# PCB-Relay-Board-V1.net
KiCad netlist of a schematic drawn in Altium Designer
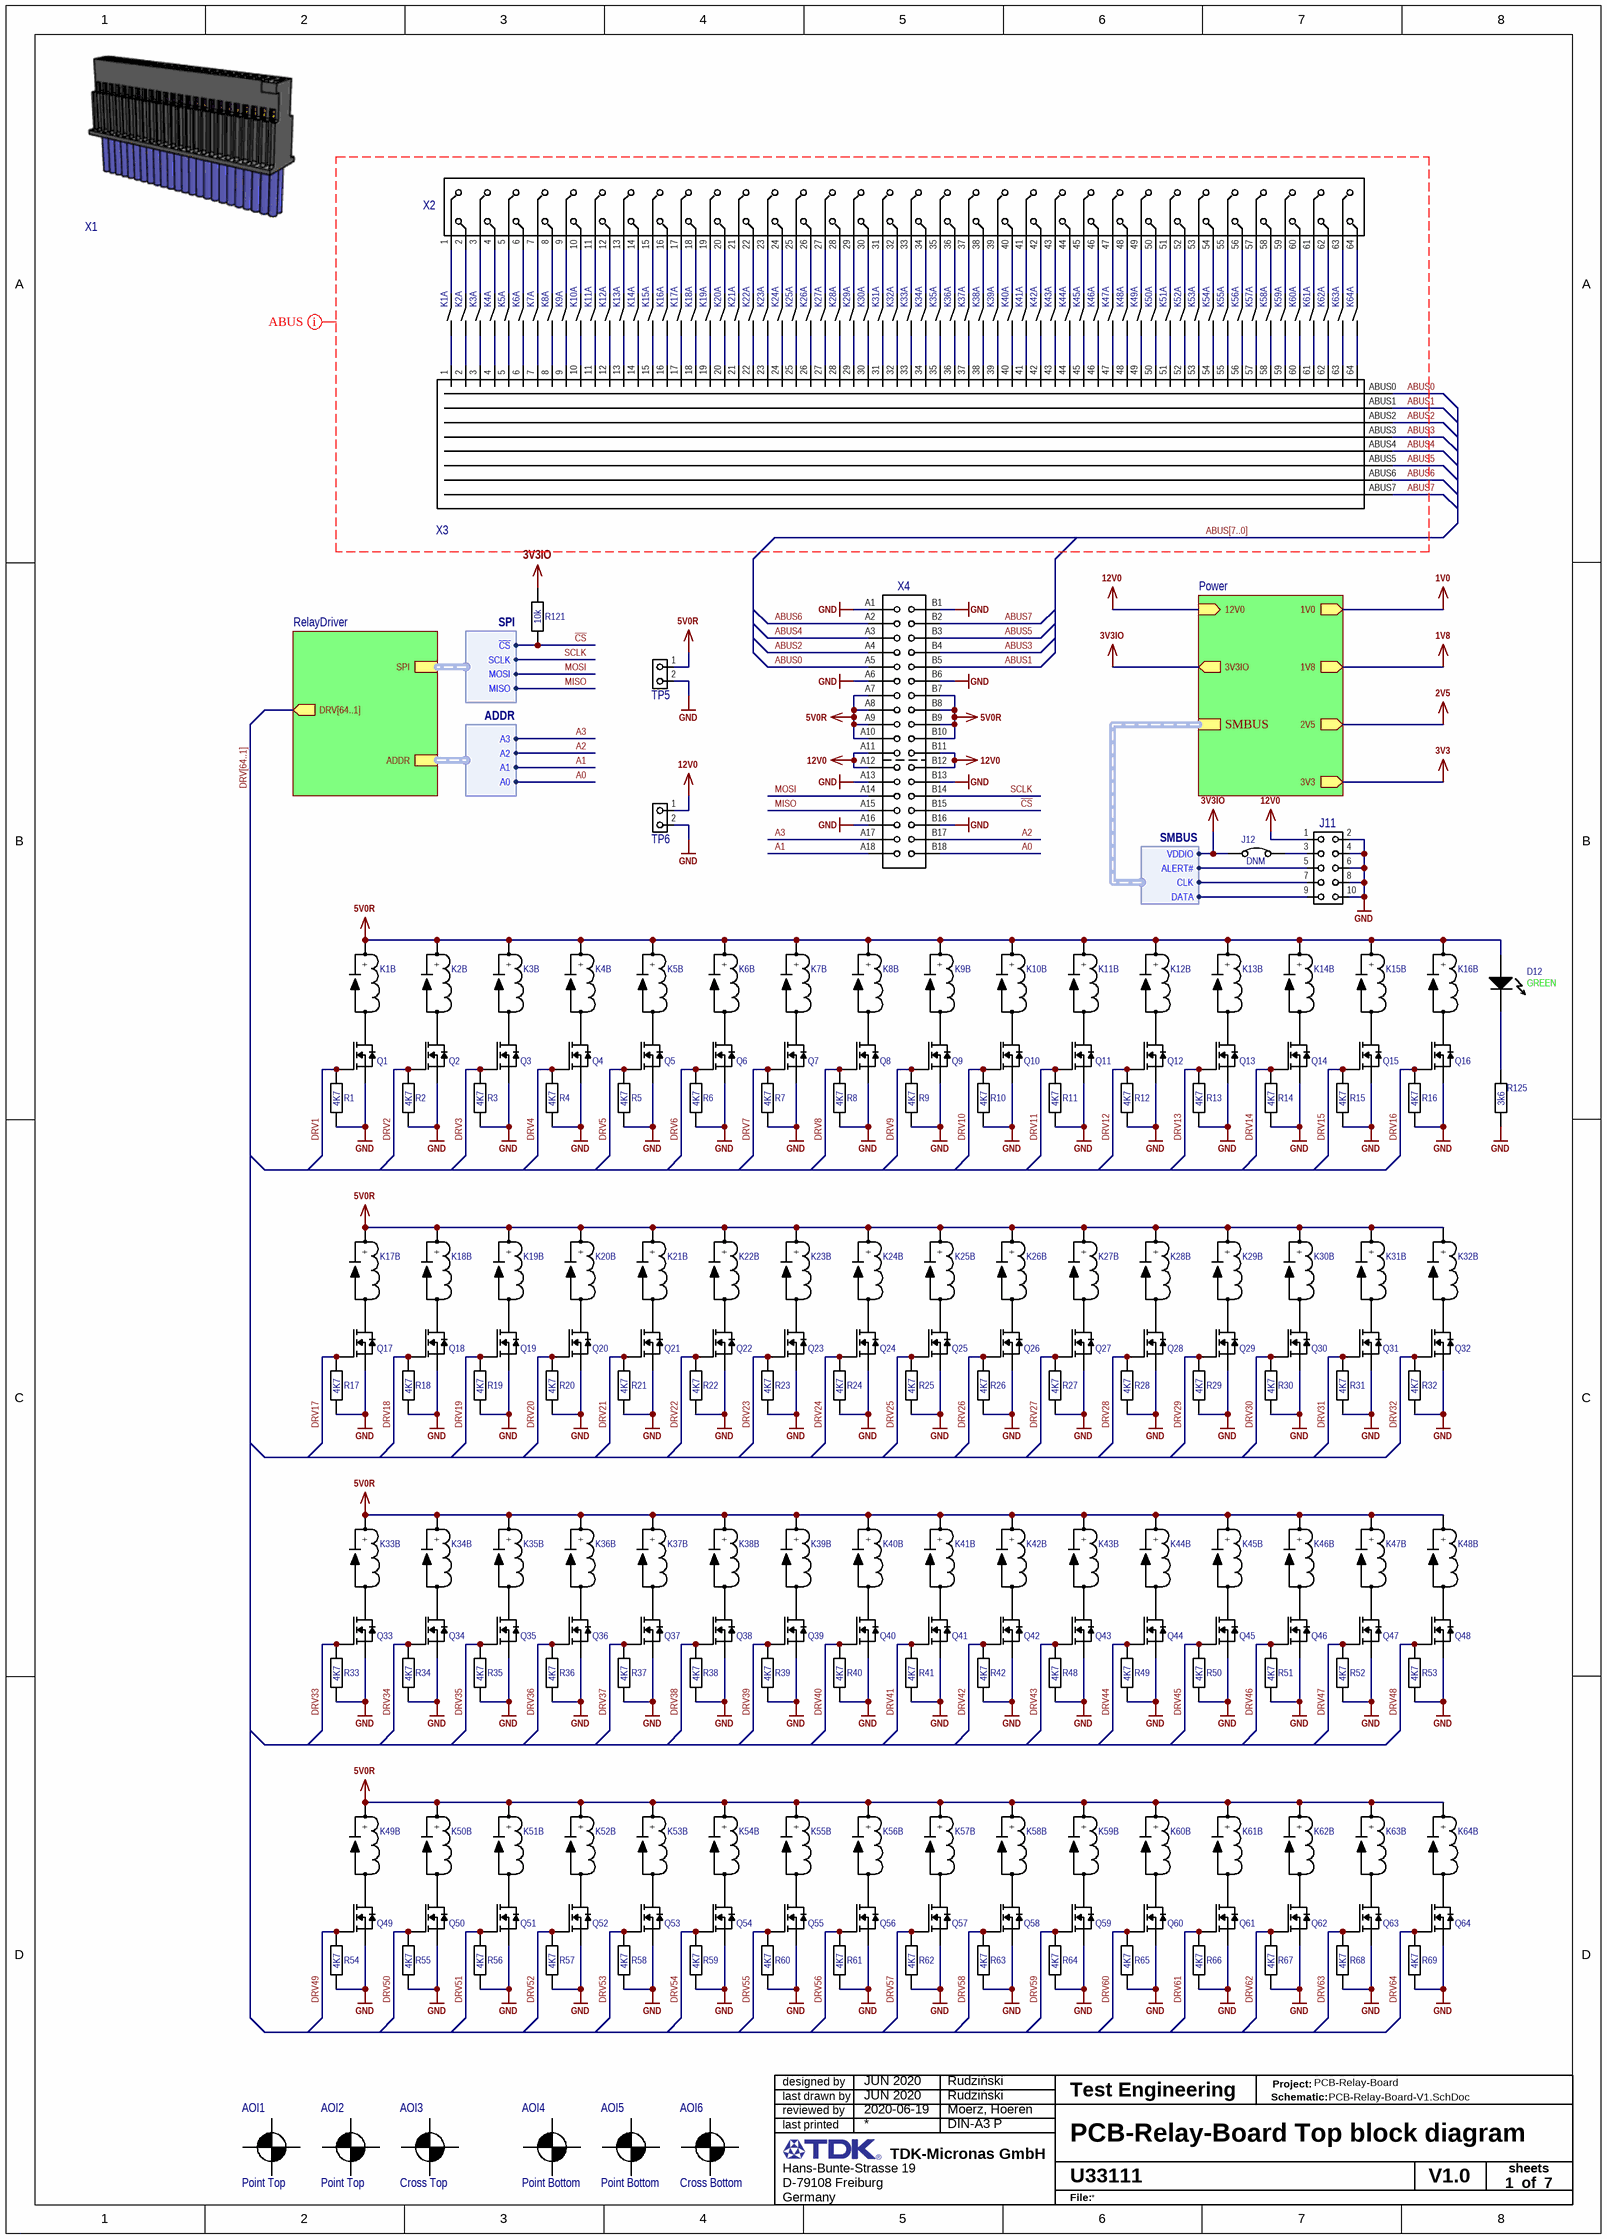
[diagram p0: PCB-Relay-Board-V1.SchDoc]

(export (version "E")
  (design (tool "Eeschema 10.0.6"))
  (components
    (comp (ref "AOI1")
      (value "AOI")
      (footprint "Fiducial Point")
      (description "Assembly AOI")
      (fields (field (name "SHAPE") "Point Top") (field (name "13. CREATED DATE/NAME") "AUG2018/Hören"))
      (libsource (lib "chickenfood") (part "Fiducial"))
    )
    (comp (ref "AOI2")
      (value "AOI")
      (footprint "Fiducial Point")
      (description "Assembly AOI")
      (fields (field (name "SHAPE") "Point Top") (field (name "13. CREATED DATE/NAME") "AUG2018/Hören"))
      (libsource (lib "chickenfood") (part "Fiducial"))
    )
    (comp (ref "AOI3")
      (value "AOI")
      (footprint "Fiducial Cross")
      (description "Assembly AOI")
      (fields (field (name "SHAPE") "Cross Top") (field (name "13. CREATED DATE/NAME") "AUG2018/Hören"))
      (libsource (lib "chickenfood") (part "Fiducial"))
    )
    (comp (ref "AOI4")
      (value "AOI")
      (footprint "Fiducial Point")
      (description "Assembly AOI")
      (fields (field (name "SHAPE") "Point Bottom") (field (name "13. CREATED DATE/NAME") "AUG2018/Hören"))
      (libsource (lib "chickenfood") (part "Fiducial"))
    )
    (comp (ref "AOI5")
      (value "AOI")
      (footprint "Fiducial Point")
      (description "Assembly AOI")
      (fields (field (name "SHAPE") "Point Bottom") (field (name "13. CREATED DATE/NAME") "AUG2018/Hören"))
      (libsource (lib "chickenfood") (part "Fiducial"))
    )
    (comp (ref "AOI6")
      (value "AOI")
      (footprint "Fiducial Cross")
      (description "Assembly AOI")
      (fields (field (name "SHAPE") "Cross Bottom") (field (name "13. CREATED DATE/NAME") "AUG2018/Hören"))
      (libsource (lib "chickenfood") (part "Fiducial"))
    )
    (comp (ref "D12")
      (value "D")
      (footprint "L0603G")
      (description "LED GREEN DIFFUSED 0603 SMD")
      (fields
        (field (name "02. DISTRIBUTOR PART NUMBER") "475-2709-6-ND")
        (field (name "07. MANUFACTURER  PART NUMBER") "LG L29K-G2J1-24-Z")
        (field (name "COLOR") "GREEN")
        (field (name "13. CREATED DATE/NAME") "AUG2018/Hören")
      )
      (libsource (lib "chickenfood") (part "LED"))
    )
    (comp (ref "J11")
      (value "J")
      (footprint "Header 100mil 5x2")
      (description ".100\" High-Temp Variable Post Height Terminal Strip")
      (fields
        (field (name "02. DISTRIBUTOR PART NUMBER") "HMTSW-105-07-G-D-240")
        (field (name "13. CREATED DATE/NAME") "AUG2018/Hören")
      )
      (libsource (lib "PCB-Tester-Board-V1") (part "Header 5x2Pins 100mil"))
    )
    (comp (ref "J12")
      (value "DNM")
      (footprint "JumperSMD")
      (description "RES SMD 0 OHM JUMPER 1/10W 0603")
      (fields
        (field (name "02. DISTRIBUTOR PART NUMBER") "311-0.0GRDKR-ND")
        (field (name "07. MANUFACTURER  PART NUMBER") "RC0603JR-070RL")
      )
      (libsource (lib "chickenfood") (part "Jumper SMD"))
    )
    (comp (ref "K1")
      (value "K")
      (footprint "118-1A")
      (description "5V Signal Relais, Normal Open")
      (fields
        (field (name "02. DISTRIBUTOR PART NUMBER") "118-1-A-5/2D")
        (field (name "13. CREATED DATE/NAME") "20.12.17 S. Kaiser")
      )
      (libsource (lib "") (part "118-1-A-5/2D_1"))
    )
    (comp (ref "K2")
      (value "K")
      (footprint "118-1A")
      (description "5V Signal Relais, Normal Open")
      (fields
        (field (name "02. DISTRIBUTOR PART NUMBER") "118-1-A-5/2D")
        (field (name "13. CREATED DATE/NAME") "20.12.17 S. Kaiser")
      )
      (libsource (lib "") (part "118-1-A-5/2D_1"))
    )
    (comp (ref "K3")
      (value "K")
      (footprint "118-1A")
      (description "5V Signal Relais, Normal Open")
      (fields
        (field (name "02. DISTRIBUTOR PART NUMBER") "118-1-A-5/2D")
        (field (name "13. CREATED DATE/NAME") "20.12.17 S. Kaiser")
      )
      (libsource (lib "") (part "118-1-A-5/2D_1"))
    )
    (comp (ref "K4")
      (value "K")
      (footprint "118-1A")
      (description "5V Signal Relais, Normal Open")
      (fields
        (field (name "02. DISTRIBUTOR PART NUMBER") "118-1-A-5/2D")
        (field (name "13. CREATED DATE/NAME") "20.12.17 S. Kaiser")
      )
      (libsource (lib "") (part "118-1-A-5/2D_1"))
    )
    (comp (ref "K5")
      (value "K")
      (footprint "118-1A")
      (description "5V Signal Relais, Normal Open")
      (fields
        (field (name "02. DISTRIBUTOR PART NUMBER") "118-1-A-5/2D")
        (field (name "13. CREATED DATE/NAME") "20.12.17 S. Kaiser")
      )
      (libsource (lib "chickenfood") (part "118-1-A-5/2D"))
    )
    (comp (ref "K6")
      (value "K")
      (footprint "118-1A")
      (description "5V Signal Relais, Normal Open")
      (fields
        (field (name "02. DISTRIBUTOR PART NUMBER") "118-1-A-5/2D")
        (field (name "13. CREATED DATE/NAME") "20.12.17 S. Kaiser")
      )
      (libsource (lib "chickenfood") (part "118-1-A-5/2D"))
    )
    (comp (ref "K7")
      (value "K")
      (footprint "118-1A")
      (description "5V Signal Relais, Normal Open")
      (fields
        (field (name "02. DISTRIBUTOR PART NUMBER") "118-1-A-5/2D")
        (field (name "13. CREATED DATE/NAME") "20.12.17 S. Kaiser")
      )
      (libsource (lib "chickenfood") (part "118-1-A-5/2D"))
    )
    (comp (ref "K8")
      (value "K")
      (footprint "118-1A")
      (description "5V Signal Relais, Normal Open")
      (fields
        (field (name "02. DISTRIBUTOR PART NUMBER") "118-1-A-5/2D")
        (field (name "13. CREATED DATE/NAME") "20.12.17 S. Kaiser")
      )
      (libsource (lib "") (part "118-1-A-5/2D_1"))
    )
    (comp (ref "K9")
      (value "K")
      (footprint "118-1A")
      (description "5V Signal Relais, Normal Open")
      (fields
        (field (name "02. DISTRIBUTOR PART NUMBER") "118-1-A-5/2D")
        (field (name "13. CREATED DATE/NAME") "20.12.17 S. Kaiser")
      )
      (libsource (lib "chickenfood") (part "118-1-A-5/2D"))
    )
    (comp (ref "K10")
      (value "K")
      (footprint "118-1A")
      (description "5V Signal Relais, Normal Open")
      (fields
        (field (name "02. DISTRIBUTOR PART NUMBER") "118-1-A-5/2D")
        (field (name "13. CREATED DATE/NAME") "20.12.17 S. Kaiser")
      )
      (libsource (lib "chickenfood") (part "118-1-A-5/2D"))
    )
    (comp (ref "K11")
      (value "K")
      (footprint "118-1A")
      (description "5V Signal Relais, Normal Open")
      (fields
        (field (name "02. DISTRIBUTOR PART NUMBER") "118-1-A-5/2D")
        (field (name "13. CREATED DATE/NAME") "20.12.17 S. Kaiser")
      )
      (libsource (lib "chickenfood") (part "118-1-A-5/2D"))
    )
    (comp (ref "K12")
      (value "K")
      (footprint "118-1A")
      (description "5V Signal Relais, Normal Open")
      (fields
        (field (name "02. DISTRIBUTOR PART NUMBER") "118-1-A-5/2D")
        (field (name "13. CREATED DATE/NAME") "20.12.17 S. Kaiser")
      )
      (libsource (lib "chickenfood") (part "118-1-A-5/2D"))
    )
    (comp (ref "K13")
      (value "K")
      (footprint "118-1A")
      (description "5V Signal Relais, Normal Open")
      (fields
        (field (name "02. DISTRIBUTOR PART NUMBER") "118-1-A-5/2D")
        (field (name "13. CREATED DATE/NAME") "20.12.17 S. Kaiser")
      )
      (libsource (lib "") (part "118-1-A-5/2D_1"))
    )
    (comp (ref "K14")
      (value "K")
      (footprint "118-1A")
      (description "5V Signal Relais, Normal Open")
      (fields
        (field (name "02. DISTRIBUTOR PART NUMBER") "118-1-A-5/2D")
        (field (name "13. CREATED DATE/NAME") "20.12.17 S. Kaiser")
      )
      (libsource (lib "chickenfood") (part "118-1-A-5/2D"))
    )
    (comp (ref "K15")
      (value "K")
      (footprint "118-1A")
      (description "5V Signal Relais, Normal Open")
      (fields
        (field (name "02. DISTRIBUTOR PART NUMBER") "118-1-A-5/2D")
        (field (name "13. CREATED DATE/NAME") "20.12.17 S. Kaiser")
      )
      (libsource (lib "") (part "118-1-A-5/2D_1"))
    )
    (comp (ref "K16")
      (value "K")
      (footprint "118-1A")
      (description "5V Signal Relais, Normal Open")
      (fields
        (field (name "02. DISTRIBUTOR PART NUMBER") "118-1-A-5/2D")
        (field (name "13. CREATED DATE/NAME") "20.12.17 S. Kaiser")
      )
      (libsource (lib "chickenfood") (part "118-1-A-5/2D"))
    )
    (comp (ref "K17")
      (value "K")
      (footprint "118-1A")
      (description "5V Signal Relais, Normal Open")
      (fields
        (field (name "02. DISTRIBUTOR PART NUMBER") "118-1-A-5/2D")
        (field (name "13. CREATED DATE/NAME") "20.12.17 S. Kaiser")
      )
      (libsource (lib "chickenfood") (part "118-1-A-5/2D"))
    )
    (comp (ref "K18")
      (value "K")
      (footprint "118-1A")
      (description "5V Signal Relais, Normal Open")
      (fields
        (field (name "02. DISTRIBUTOR PART NUMBER") "118-1-A-5/2D")
        (field (name "13. CREATED DATE/NAME") "20.12.17 S. Kaiser")
      )
      (libsource (lib "") (part "118-1-A-5/2D_1"))
    )
    (comp (ref "K19")
      (value "K")
      (footprint "118-1A")
      (description "5V Signal Relais, Normal Open")
      (fields
        (field (name "02. DISTRIBUTOR PART NUMBER") "118-1-A-5/2D")
        (field (name "13. CREATED DATE/NAME") "20.12.17 S. Kaiser")
      )
      (libsource (lib "chickenfood") (part "118-1-A-5/2D"))
    )
    (comp (ref "K20")
      (value "K")
      (footprint "118-1A")
      (description "5V Signal Relais, Normal Open")
      (fields
        (field (name "02. DISTRIBUTOR PART NUMBER") "118-1-A-5/2D")
        (field (name "13. CREATED DATE/NAME") "20.12.17 S. Kaiser")
      )
      (libsource (lib "") (part "118-1-A-5/2D_1"))
    )
    (comp (ref "K21")
      (value "K")
      (footprint "118-1A")
      (description "5V Signal Relais, Normal Open")
      (fields
        (field (name "02. DISTRIBUTOR PART NUMBER") "118-1-A-5/2D")
        (field (name "13. CREATED DATE/NAME") "20.12.17 S. Kaiser")
      )
      (libsource (lib "chickenfood") (part "118-1-A-5/2D"))
    )
    (comp (ref "K22")
      (value "K")
      (footprint "118-1A")
      (description "5V Signal Relais, Normal Open")
      (fields
        (field (name "02. DISTRIBUTOR PART NUMBER") "118-1-A-5/2D")
        (field (name "13. CREATED DATE/NAME") "20.12.17 S. Kaiser")
      )
      (libsource (lib "") (part "118-1-A-5/2D_1"))
    )
    (comp (ref "K23")
      (value "K")
      (footprint "118-1A")
      (description "5V Signal Relais, Normal Open")
      (fields
        (field (name "02. DISTRIBUTOR PART NUMBER") "118-1-A-5/2D")
        (field (name "13. CREATED DATE/NAME") "20.12.17 S. Kaiser")
      )
      (libsource (lib "") (part "118-1-A-5/2D_1"))
    )
    (comp (ref "K24")
      (value "K")
      (footprint "118-1A")
      (description "5V Signal Relais, Normal Open")
      (fields
        (field (name "02. DISTRIBUTOR PART NUMBER") "118-1-A-5/2D")
        (field (name "13. CREATED DATE/NAME") "20.12.17 S. Kaiser")
      )
      (libsource (lib "chickenfood") (part "118-1-A-5/2D"))
    )
    (comp (ref "K25")
      (value "K")
      (footprint "118-1A")
      (description "5V Signal Relais, Normal Open")
      (fields
        (field (name "02. DISTRIBUTOR PART NUMBER") "118-1-A-5/2D")
        (field (name "13. CREATED DATE/NAME") "20.12.17 S. Kaiser")
      )
      (libsource (lib "") (part "118-1-A-5/2D_1"))
    )
    (comp (ref "K26")
      (value "K")
      (footprint "118-1A")
      (description "5V Signal Relais, Normal Open")
      (fields
        (field (name "02. DISTRIBUTOR PART NUMBER") "118-1-A-5/2D")
        (field (name "13. CREATED DATE/NAME") "20.12.17 S. Kaiser")
      )
      (libsource (lib "chickenfood") (part "118-1-A-5/2D"))
    )
    (comp (ref "K27")
      (value "K")
      (footprint "118-1A")
      (description "5V Signal Relais, Normal Open")
      (fields
        (field (name "02. DISTRIBUTOR PART NUMBER") "118-1-A-5/2D")
        (field (name "13. CREATED DATE/NAME") "20.12.17 S. Kaiser")
      )
      (libsource (lib "") (part "118-1-A-5/2D_1"))
    )
    (comp (ref "K28")
      (value "K")
      (footprint "118-1A")
      (description "5V Signal Relais, Normal Open")
      (fields
        (field (name "02. DISTRIBUTOR PART NUMBER") "118-1-A-5/2D")
        (field (name "13. CREATED DATE/NAME") "20.12.17 S. Kaiser")
      )
      (libsource (lib "chickenfood") (part "118-1-A-5/2D"))
    )
    (comp (ref "K29")
      (value "K")
      (footprint "118-1A")
      (description "5V Signal Relais, Normal Open")
      (fields
        (field (name "02. DISTRIBUTOR PART NUMBER") "118-1-A-5/2D")
        (field (name "13. CREATED DATE/NAME") "20.12.17 S. Kaiser")
      )
      (libsource (lib "chickenfood") (part "118-1-A-5/2D"))
    )
    (comp (ref "K30")
      (value "K")
      (footprint "118-1A")
      (description "5V Signal Relais, Normal Open")
      (fields
        (field (name "02. DISTRIBUTOR PART NUMBER") "118-1-A-5/2D")
        (field (name "13. CREATED DATE/NAME") "20.12.17 S. Kaiser")
      )
      (libsource (lib "") (part "118-1-A-5/2D_1"))
    )
    (comp (ref "K31")
      (value "K")
      (footprint "118-1A")
      (description "5V Signal Relais, Normal Open")
      (fields
        (field (name "02. DISTRIBUTOR PART NUMBER") "118-1-A-5/2D")
        (field (name "13. CREATED DATE/NAME") "20.12.17 S. Kaiser")
      )
      (libsource (lib "") (part "118-1-A-5/2D_1"))
    )
    (comp (ref "K32")
      (value "K")
      (footprint "118-1A")
      (description "5V Signal Relais, Normal Open")
      (fields
        (field (name "02. DISTRIBUTOR PART NUMBER") "118-1-A-5/2D")
        (field (name "13. CREATED DATE/NAME") "20.12.17 S. Kaiser")
      )
      (libsource (lib "") (part "118-1-A-5/2D_1"))
    )
    (comp (ref "K33")
      (value "K")
      (footprint "118-1A")
      (description "5V Signal Relais, Normal Open")
      (fields
        (field (name "02. DISTRIBUTOR PART NUMBER") "118-1-A-5/2D")
        (field (name "13. CREATED DATE/NAME") "20.12.17 S. Kaiser")
      )
      (libsource (lib "chickenfood") (part "118-1-A-5/2D"))
    )
    (comp (ref "K34")
      (value "K")
      (footprint "118-1A")
      (description "5V Signal Relais, Normal Open")
      (fields
        (field (name "02. DISTRIBUTOR PART NUMBER") "118-1-A-5/2D")
        (field (name "13. CREATED DATE/NAME") "20.12.17 S. Kaiser")
      )
      (libsource (lib "chickenfood") (part "118-1-A-5/2D"))
    )
    (comp (ref "K35")
      (value "K")
      (footprint "118-1A")
      (description "5V Signal Relais, Normal Open")
      (fields
        (field (name "02. DISTRIBUTOR PART NUMBER") "118-1-A-5/2D")
        (field (name "13. CREATED DATE/NAME") "20.12.17 S. Kaiser")
      )
      (libsource (lib "") (part "118-1-A-5/2D_1"))
    )
    (comp (ref "K36")
      (value "K")
      (footprint "118-1A")
      (description "5V Signal Relais, Normal Open")
      (fields
        (field (name "02. DISTRIBUTOR PART NUMBER") "118-1-A-5/2D")
        (field (name "13. CREATED DATE/NAME") "20.12.17 S. Kaiser")
      )
      (libsource (lib "chickenfood") (part "118-1-A-5/2D"))
    )
    (comp (ref "K37")
      (value "K")
      (footprint "118-1A")
      (description "5V Signal Relais, Normal Open")
      (fields
        (field (name "02. DISTRIBUTOR PART NUMBER") "118-1-A-5/2D")
        (field (name "13. CREATED DATE/NAME") "20.12.17 S. Kaiser")
      )
      (libsource (lib "chickenfood") (part "118-1-A-5/2D"))
    )
    (comp (ref "K38")
      (value "K")
      (footprint "118-1A")
      (description "5V Signal Relais, Normal Open")
      (fields
        (field (name "02. DISTRIBUTOR PART NUMBER") "118-1-A-5/2D")
        (field (name "13. CREATED DATE/NAME") "20.12.17 S. Kaiser")
      )
      (libsource (lib "") (part "118-1-A-5/2D_1"))
    )
    (comp (ref "K39")
      (value "K")
      (footprint "118-1A")
      (description "5V Signal Relais, Normal Open")
      (fields
        (field (name "02. DISTRIBUTOR PART NUMBER") "118-1-A-5/2D")
        (field (name "13. CREATED DATE/NAME") "20.12.17 S. Kaiser")
      )
      (libsource (lib "") (part "118-1-A-5/2D_1"))
    )
    (comp (ref "K40")
      (value "K")
      (footprint "118-1A")
      (description "5V Signal Relais, Normal Open")
      (fields
        (field (name "02. DISTRIBUTOR PART NUMBER") "118-1-A-5/2D")
        (field (name "13. CREATED DATE/NAME") "20.12.17 S. Kaiser")
      )
      (libsource (lib "chickenfood") (part "118-1-A-5/2D"))
    )
    (comp (ref "K41")
      (value "K")
      (footprint "118-1A")
      (description "5V Signal Relais, Normal Open")
      (fields
        (field (name "02. DISTRIBUTOR PART NUMBER") "118-1-A-5/2D")
        (field (name "13. CREATED DATE/NAME") "20.12.17 S. Kaiser")
      )
      (libsource (lib "chickenfood") (part "118-1-A-5/2D"))
    )
    (comp (ref "K42")
      (value "K")
      (footprint "118-1A")
      (description "5V Signal Relais, Normal Open")
      (fields
        (field (name "02. DISTRIBUTOR PART NUMBER") "118-1-A-5/2D")
        (field (name "13. CREATED DATE/NAME") "20.12.17 S. Kaiser")
      )
      (libsource (lib "") (part "118-1-A-5/2D_1"))
    )
    (comp (ref "K43")
      (value "K")
      (footprint "118-1A")
      (description "5V Signal Relais, Normal Open")
      (fields
        (field (name "02. DISTRIBUTOR PART NUMBER") "118-1-A-5/2D")
        (field (name "13. CREATED DATE/NAME") "20.12.17 S. Kaiser")
      )
      (libsource (lib "chickenfood") (part "118-1-A-5/2D"))
    )
    (comp (ref "K44")
      (value "K")
      (footprint "118-1A")
      (description "5V Signal Relais, Normal Open")
      (fields
        (field (name "02. DISTRIBUTOR PART NUMBER") "118-1-A-5/2D")
        (field (name "13. CREATED DATE/NAME") "20.12.17 S. Kaiser")
      )
      (libsource (lib "") (part "118-1-A-5/2D_1"))
    )
    (comp (ref "K45")
      (value "K")
      (footprint "118-1A")
      (description "5V Signal Relais, Normal Open")
      (fields
        (field (name "02. DISTRIBUTOR PART NUMBER") "118-1-A-5/2D")
        (field (name "13. CREATED DATE/NAME") "20.12.17 S. Kaiser")
      )
      (libsource (lib "chickenfood") (part "118-1-A-5/2D"))
    )
    (comp (ref "K46")
      (value "K")
      (footprint "118-1A")
      (description "5V Signal Relais, Normal Open")
      (fields
        (field (name "02. DISTRIBUTOR PART NUMBER") "118-1-A-5/2D")
        (field (name "13. CREATED DATE/NAME") "20.12.17 S. Kaiser")
      )
      (libsource (lib "chickenfood") (part "118-1-A-5/2D"))
    )
    (comp (ref "K47")
      (value "K")
      (footprint "118-1A")
      (description "5V Signal Relais, Normal Open")
      (fields
        (field (name "02. DISTRIBUTOR PART NUMBER") "118-1-A-5/2D")
        (field (name "13. CREATED DATE/NAME") "20.12.17 S. Kaiser")
      )
      (libsource (lib "chickenfood") (part "118-1-A-5/2D"))
    )
    (comp (ref "K48")
      (value "K")
      (footprint "118-1A")
      (description "5V Signal Relais, Normal Open")
      (fields
        (field (name "02. DISTRIBUTOR PART NUMBER") "118-1-A-5/2D")
        (field (name "13. CREATED DATE/NAME") "20.12.17 S. Kaiser")
      )
      (libsource (lib "chickenfood") (part "118-1-A-5/2D"))
    )
    (comp (ref "K49")
      (value "K")
      (footprint "118-1A")
      (description "5V Signal Relais, Normal Open")
      (fields
        (field (name "02. DISTRIBUTOR PART NUMBER") "118-1-A-5/2D")
        (field (name "13. CREATED DATE/NAME") "20.12.17 S. Kaiser")
      )
      (libsource (lib "chickenfood") (part "118-1-A-5/2D"))
    )
    (comp (ref "K50")
      (value "K")
      (footprint "118-1A")
      (description "5V Signal Relais, Normal Open")
      (fields
        (field (name "02. DISTRIBUTOR PART NUMBER") "118-1-A-5/2D")
        (field (name "13. CREATED DATE/NAME") "20.12.17 S. Kaiser")
      )
      (libsource (lib "chickenfood") (part "118-1-A-5/2D"))
    )
    (comp (ref "K51")
      (value "K")
      (footprint "118-1A")
      (description "5V Signal Relais, Normal Open")
      (fields
        (field (name "02. DISTRIBUTOR PART NUMBER") "118-1-A-5/2D")
        (field (name "13. CREATED DATE/NAME") "20.12.17 S. Kaiser")
      )
      (libsource (lib "chickenfood") (part "118-1-A-5/2D"))
    )
    (comp (ref "K52")
      (value "K")
      (footprint "118-1A")
      (description "5V Signal Relais, Normal Open")
      (fields
        (field (name "02. DISTRIBUTOR PART NUMBER") "118-1-A-5/2D")
        (field (name "13. CREATED DATE/NAME") "20.12.17 S. Kaiser")
      )
      (libsource (lib "chickenfood") (part "118-1-A-5/2D"))
    )
    (comp (ref "K53")
      (value "K")
      (footprint "118-1A")
      (description "5V Signal Relais, Normal Open")
      (fields
        (field (name "02. DISTRIBUTOR PART NUMBER") "118-1-A-5/2D")
        (field (name "13. CREATED DATE/NAME") "20.12.17 S. Kaiser")
      )
      (libsource (lib "chickenfood") (part "118-1-A-5/2D"))
    )
    (comp (ref "K54")
      (value "K")
      (footprint "118-1A")
      (description "5V Signal Relais, Normal Open")
      (fields
        (field (name "02. DISTRIBUTOR PART NUMBER") "118-1-A-5/2D")
        (field (name "13. CREATED DATE/NAME") "20.12.17 S. Kaiser")
      )
      (libsource (lib "chickenfood") (part "118-1-A-5/2D"))
    )
    (comp (ref "K55")
      (value "K")
      (footprint "118-1A")
      (description "5V Signal Relais, Normal Open")
      (fields
        (field (name "02. DISTRIBUTOR PART NUMBER") "118-1-A-5/2D")
        (field (name "13. CREATED DATE/NAME") "20.12.17 S. Kaiser")
      )
      (libsource (lib "") (part "118-1-A-5/2D_1"))
    )
    (comp (ref "K56")
      (value "K")
      (footprint "118-1A")
      (description "5V Signal Relais, Normal Open")
      (fields
        (field (name "02. DISTRIBUTOR PART NUMBER") "118-1-A-5/2D")
        (field (name "13. CREATED DATE/NAME") "20.12.17 S. Kaiser")
      )
      (libsource (lib "") (part "118-1-A-5/2D_1"))
    )
    (comp (ref "K57")
      (value "K")
      (footprint "118-1A")
      (description "5V Signal Relais, Normal Open")
      (fields
        (field (name "02. DISTRIBUTOR PART NUMBER") "118-1-A-5/2D")
        (field (name "13. CREATED DATE/NAME") "20.12.17 S. Kaiser")
      )
      (libsource (lib "") (part "118-1-A-5/2D_1"))
    )
    (comp (ref "K58")
      (value "K")
      (footprint "118-1A")
      (description "5V Signal Relais, Normal Open")
      (fields
        (field (name "02. DISTRIBUTOR PART NUMBER") "118-1-A-5/2D")
        (field (name "13. CREATED DATE/NAME") "20.12.17 S. Kaiser")
      )
      (libsource (lib "") (part "118-1-A-5/2D_1"))
    )
    (comp (ref "K59")
      (value "K")
      (footprint "118-1A")
      (description "5V Signal Relais, Normal Open")
      (fields
        (field (name "02. DISTRIBUTOR PART NUMBER") "118-1-A-5/2D")
        (field (name "13. CREATED DATE/NAME") "20.12.17 S. Kaiser")
      )
      (libsource (lib "chickenfood") (part "118-1-A-5/2D"))
    )
    (comp (ref "K60")
      (value "K")
      (footprint "118-1A")
      (description "5V Signal Relais, Normal Open")
      (fields
        (field (name "02. DISTRIBUTOR PART NUMBER") "118-1-A-5/2D")
        (field (name "13. CREATED DATE/NAME") "20.12.17 S. Kaiser")
      )
      (libsource (lib "") (part "118-1-A-5/2D_1"))
    )
    (comp (ref "K61")
      (value "K")
      (footprint "118-1A")
      (description "5V Signal Relais, Normal Open")
      (fields
        (field (name "02. DISTRIBUTOR PART NUMBER") "118-1-A-5/2D")
        (field (name "13. CREATED DATE/NAME") "20.12.17 S. Kaiser")
      )
      (libsource (lib "") (part "118-1-A-5/2D_1"))
    )
    (comp (ref "K62")
      (value "K")
      (footprint "118-1A")
      (description "5V Signal Relais, Normal Open")
      (fields
        (field (name "02. DISTRIBUTOR PART NUMBER") "118-1-A-5/2D")
        (field (name "13. CREATED DATE/NAME") "20.12.17 S. Kaiser")
      )
      (libsource (lib "") (part "118-1-A-5/2D_1"))
    )
    (comp (ref "K63")
      (value "K")
      (footprint "118-1A")
      (description "5V Signal Relais, Normal Open")
      (fields
        (field (name "02. DISTRIBUTOR PART NUMBER") "118-1-A-5/2D")
        (field (name "13. CREATED DATE/NAME") "20.12.17 S. Kaiser")
      )
      (libsource (lib "chickenfood") (part "118-1-A-5/2D"))
    )
    (comp (ref "K64")
      (value "K")
      (footprint "118-1A")
      (description "5V Signal Relais, Normal Open")
      (fields
        (field (name "02. DISTRIBUTOR PART NUMBER") "118-1-A-5/2D")
        (field (name "13. CREATED DATE/NAME") "20.12.17 S. Kaiser")
      )
      (libsource (lib "") (part "118-1-A-5/2D_1"))
    )
    (comp (ref "Q1")
      (value "Q")
      (footprint "SOT23-3")
      (description "MOSFET N-CH 25V 680MA SOT-23")
      (fields
        (field (name "02. DISTRIBUTOR PART NUMBER") "FDV303NDKR-ND")
        (field (name "07. MANUFACTURER  PART NUMBER") "FDV303N")
        (field (name "13. CREATED DATE/NAME") "AUG 2018 / Hören")
      )
      (libsource (lib "SCT8-Board1") (part "FDV303N"))
    )
    (comp (ref "Q2")
      (value "Q")
      (footprint "SOT23-3")
      (description "MOSFET N-CH 25V 680MA SOT-23")
      (fields
        (field (name "02. DISTRIBUTOR PART NUMBER") "FDV303NDKR-ND")
        (field (name "07. MANUFACTURER  PART NUMBER") "FDV303N")
        (field (name "13. CREATED DATE/NAME") "AUG 2018 / Hören")
      )
      (libsource (lib "SCT8-Board1") (part "FDV303N"))
    )
    (comp (ref "Q3")
      (value "Q")
      (footprint "SOT23-3")
      (description "MOSFET N-CH 25V 680MA SOT-23")
      (fields
        (field (name "02. DISTRIBUTOR PART NUMBER") "FDV303NDKR-ND")
        (field (name "07. MANUFACTURER  PART NUMBER") "FDV303N")
        (field (name "13. CREATED DATE/NAME") "AUG 2018 / Hören")
      )
      (libsource (lib "SCT8-Board1") (part "FDV303N"))
    )
    (comp (ref "Q4")
      (value "Q")
      (footprint "SOT23-3")
      (description "MOSFET N-CH 25V 680MA SOT-23")
      (fields
        (field (name "02. DISTRIBUTOR PART NUMBER") "FDV303NDKR-ND")
        (field (name "07. MANUFACTURER  PART NUMBER") "FDV303N")
        (field (name "13. CREATED DATE/NAME") "AUG 2018 / Hören")
      )
      (libsource (lib "SCT8-Board1") (part "FDV303N"))
    )
    (comp (ref "Q5")
      (value "Q")
      (footprint "SOT23-3")
      (description "MOSFET N-CH 25V 680MA SOT-23")
      (fields
        (field (name "02. DISTRIBUTOR PART NUMBER") "FDV303NDKR-ND")
        (field (name "07. MANUFACTURER  PART NUMBER") "FDV303N")
        (field (name "13. CREATED DATE/NAME") "AUG 2018 / Hören")
      )
      (libsource (lib "SCT8-Board1") (part "FDV303N"))
    )
    (comp (ref "Q6")
      (value "Q")
      (footprint "SOT23-3")
      (description "MOSFET N-CH 25V 680MA SOT-23")
      (fields
        (field (name "02. DISTRIBUTOR PART NUMBER") "FDV303NDKR-ND")
        (field (name "07. MANUFACTURER  PART NUMBER") "FDV303N")
        (field (name "13. CREATED DATE/NAME") "AUG 2018 / Hören")
      )
      (libsource (lib "SCT8-Board1") (part "FDV303N"))
    )
    (comp (ref "Q7")
      (value "Q")
      (footprint "SOT23-3")
      (description "MOSFET N-CH 25V 680MA SOT-23")
      (fields
        (field (name "02. DISTRIBUTOR PART NUMBER") "FDV303NDKR-ND")
        (field (name "07. MANUFACTURER  PART NUMBER") "FDV303N")
        (field (name "13. CREATED DATE/NAME") "AUG 2018 / Hören")
      )
      (libsource (lib "SCT8-Board1") (part "FDV303N"))
    )
    (comp (ref "Q8")
      (value "Q")
      (footprint "SOT23-3")
      (description "MOSFET N-CH 25V 680MA SOT-23")
      (fields
        (field (name "02. DISTRIBUTOR PART NUMBER") "FDV303NDKR-ND")
        (field (name "07. MANUFACTURER  PART NUMBER") "FDV303N")
        (field (name "13. CREATED DATE/NAME") "AUG 2018 / Hören")
      )
      (libsource (lib "SCT8-Board1") (part "FDV303N"))
    )
    (comp (ref "Q9")
      (value "Q")
      (footprint "SOT23-3")
      (description "MOSFET N-CH 25V 680MA SOT-23")
      (fields
        (field (name "02. DISTRIBUTOR PART NUMBER") "FDV303NDKR-ND")
        (field (name "07. MANUFACTURER  PART NUMBER") "FDV303N")
        (field (name "13. CREATED DATE/NAME") "AUG 2018 / Hören")
      )
      (libsource (lib "SCT8-Board1") (part "FDV303N"))
    )
    (comp (ref "Q10")
      (value "Q")
      (footprint "SOT23-3")
      (description "MOSFET N-CH 25V 680MA SOT-23")
      (fields
        (field (name "02. DISTRIBUTOR PART NUMBER") "FDV303NDKR-ND")
        (field (name "07. MANUFACTURER  PART NUMBER") "FDV303N")
        (field (name "13. CREATED DATE/NAME") "AUG 2018 / Hören")
      )
      (libsource (lib "SCT8-Board1") (part "FDV303N"))
    )
    (comp (ref "Q11")
      (value "Q")
      (footprint "SOT23-3")
      (description "MOSFET N-CH 25V 680MA SOT-23")
      (fields
        (field (name "02. DISTRIBUTOR PART NUMBER") "FDV303NDKR-ND")
        (field (name "07. MANUFACTURER  PART NUMBER") "FDV303N")
        (field (name "13. CREATED DATE/NAME") "AUG 2018 / Hören")
      )
      (libsource (lib "SCT8-Board1") (part "FDV303N"))
    )
    (comp (ref "Q12")
      (value "Q")
      (footprint "SOT23-3")
      (description "MOSFET N-CH 25V 680MA SOT-23")
      (fields
        (field (name "02. DISTRIBUTOR PART NUMBER") "FDV303NDKR-ND")
        (field (name "07. MANUFACTURER  PART NUMBER") "FDV303N")
        (field (name "13. CREATED DATE/NAME") "AUG 2018 / Hören")
      )
      (libsource (lib "SCT8-Board1") (part "FDV303N"))
    )
    (comp (ref "Q13")
      (value "Q")
      (footprint "SOT23-3")
      (description "MOSFET N-CH 25V 680MA SOT-23")
      (fields
        (field (name "02. DISTRIBUTOR PART NUMBER") "FDV303NDKR-ND")
        (field (name "07. MANUFACTURER  PART NUMBER") "FDV303N")
        (field (name "13. CREATED DATE/NAME") "AUG 2018 / Hören")
      )
      (libsource (lib "SCT8-Board1") (part "FDV303N"))
    )
    (comp (ref "Q14")
      (value "Q")
      (footprint "SOT23-3")
      (description "MOSFET N-CH 25V 680MA SOT-23")
      (fields
        (field (name "02. DISTRIBUTOR PART NUMBER") "FDV303NDKR-ND")
        (field (name "07. MANUFACTURER  PART NUMBER") "FDV303N")
        (field (name "13. CREATED DATE/NAME") "AUG 2018 / Hören")
      )
      (libsource (lib "SCT8-Board1") (part "FDV303N"))
    )
    (comp (ref "Q15")
      (value "Q")
      (footprint "SOT23-3")
      (description "MOSFET N-CH 25V 680MA SOT-23")
      (fields
        (field (name "02. DISTRIBUTOR PART NUMBER") "FDV303NDKR-ND")
        (field (name "07. MANUFACTURER  PART NUMBER") "FDV303N")
        (field (name "13. CREATED DATE/NAME") "AUG 2018 / Hören")
      )
      (libsource (lib "SCT8-Board1") (part "FDV303N"))
    )
    (comp (ref "Q16")
      (value "Q")
      (footprint "SOT23-3")
      (description "MOSFET N-CH 25V 680MA SOT-23")
      (fields
        (field (name "02. DISTRIBUTOR PART NUMBER") "FDV303NDKR-ND")
        (field (name "07. MANUFACTURER  PART NUMBER") "FDV303N")
        (field (name "13. CREATED DATE/NAME") "AUG 2018 / Hören")
      )
      (libsource (lib "SCT8-Board1") (part "FDV303N"))
    )
    (comp (ref "Q17")
      (value "Q")
      (footprint "SOT23-3")
      (description "MOSFET N-CH 25V 680MA SOT-23")
      (fields
        (field (name "02. DISTRIBUTOR PART NUMBER") "FDV303NDKR-ND")
        (field (name "07. MANUFACTURER  PART NUMBER") "FDV303N")
        (field (name "13. CREATED DATE/NAME") "AUG 2018 / Hören")
      )
      (libsource (lib "SCT8-Board1") (part "FDV303N"))
    )
    (comp (ref "Q18")
      (value "Q")
      (footprint "SOT23-3")
      (description "MOSFET N-CH 25V 680MA SOT-23")
      (fields
        (field (name "02. DISTRIBUTOR PART NUMBER") "FDV303NDKR-ND")
        (field (name "07. MANUFACTURER  PART NUMBER") "FDV303N")
        (field (name "13. CREATED DATE/NAME") "AUG 2018 / Hören")
      )
      (libsource (lib "SCT8-Board1") (part "FDV303N"))
    )
    (comp (ref "Q19")
      (value "Q")
      (footprint "SOT23-3")
      (description "MOSFET N-CH 25V 680MA SOT-23")
      (fields
        (field (name "02. DISTRIBUTOR PART NUMBER") "FDV303NDKR-ND")
        (field (name "07. MANUFACTURER  PART NUMBER") "FDV303N")
        (field (name "13. CREATED DATE/NAME") "AUG 2018 / Hören")
      )
      (libsource (lib "SCT8-Board1") (part "FDV303N"))
    )
    (comp (ref "Q20")
      (value "Q")
      (footprint "SOT23-3")
      (description "MOSFET N-CH 25V 680MA SOT-23")
      (fields
        (field (name "02. DISTRIBUTOR PART NUMBER") "FDV303NDKR-ND")
        (field (name "07. MANUFACTURER  PART NUMBER") "FDV303N")
        (field (name "13. CREATED DATE/NAME") "AUG 2018 / Hören")
      )
      (libsource (lib "SCT8-Board1") (part "FDV303N"))
    )
    (comp (ref "Q21")
      (value "Q")
      (footprint "SOT23-3")
      (description "MOSFET N-CH 25V 680MA SOT-23")
      (fields
        (field (name "02. DISTRIBUTOR PART NUMBER") "FDV303NDKR-ND")
        (field (name "07. MANUFACTURER  PART NUMBER") "FDV303N")
        (field (name "13. CREATED DATE/NAME") "AUG 2018 / Hören")
      )
      (libsource (lib "SCT8-Board1") (part "FDV303N"))
    )
    (comp (ref "Q22")
      (value "Q")
      (footprint "SOT23-3")
      (description "MOSFET N-CH 25V 680MA SOT-23")
      (fields
        (field (name "02. DISTRIBUTOR PART NUMBER") "FDV303NDKR-ND")
        (field (name "07. MANUFACTURER  PART NUMBER") "FDV303N")
        (field (name "13. CREATED DATE/NAME") "AUG 2018 / Hören")
      )
      (libsource (lib "SCT8-Board1") (part "FDV303N"))
    )
    (comp (ref "Q23")
      (value "Q")
      (footprint "SOT23-3")
      (description "MOSFET N-CH 25V 680MA SOT-23")
      (fields
        (field (name "02. DISTRIBUTOR PART NUMBER") "FDV303NDKR-ND")
        (field (name "07. MANUFACTURER  PART NUMBER") "FDV303N")
        (field (name "13. CREATED DATE/NAME") "AUG 2018 / Hören")
      )
      (libsource (lib "SCT8-Board1") (part "FDV303N"))
    )
    (comp (ref "Q24")
      (value "Q")
      (footprint "SOT23-3")
      (description "MOSFET N-CH 25V 680MA SOT-23")
      (fields
        (field (name "02. DISTRIBUTOR PART NUMBER") "FDV303NDKR-ND")
        (field (name "07. MANUFACTURER  PART NUMBER") "FDV303N")
        (field (name "13. CREATED DATE/NAME") "AUG 2018 / Hören")
      )
      (libsource (lib "SCT8-Board1") (part "FDV303N"))
    )
    (comp (ref "Q25")
      (value "Q")
      (footprint "SOT23-3")
      (description "MOSFET N-CH 25V 680MA SOT-23")
      (fields
        (field (name "02. DISTRIBUTOR PART NUMBER") "FDV303NDKR-ND")
        (field (name "07. MANUFACTURER  PART NUMBER") "FDV303N")
        (field (name "13. CREATED DATE/NAME") "AUG 2018 / Hören")
      )
      (libsource (lib "SCT8-Board1") (part "FDV303N"))
    )
    (comp (ref "Q26")
      (value "Q")
      (footprint "SOT23-3")
      (description "MOSFET N-CH 25V 680MA SOT-23")
      (fields
        (field (name "02. DISTRIBUTOR PART NUMBER") "FDV303NDKR-ND")
        (field (name "07. MANUFACTURER  PART NUMBER") "FDV303N")
        (field (name "13. CREATED DATE/NAME") "AUG 2018 / Hören")
      )
      (libsource (lib "SCT8-Board1") (part "FDV303N"))
    )
    (comp (ref "Q27")
      (value "Q")
      (footprint "SOT23-3")
      (description "MOSFET N-CH 25V 680MA SOT-23")
      (fields
        (field (name "02. DISTRIBUTOR PART NUMBER") "FDV303NDKR-ND")
        (field (name "07. MANUFACTURER  PART NUMBER") "FDV303N")
        (field (name "13. CREATED DATE/NAME") "AUG 2018 / Hören")
      )
      (libsource (lib "SCT8-Board1") (part "FDV303N"))
    )
    (comp (ref "Q28")
      (value "Q")
      (footprint "SOT23-3")
      (description "MOSFET N-CH 25V 680MA SOT-23")
      (fields
        (field (name "02. DISTRIBUTOR PART NUMBER") "FDV303NDKR-ND")
        (field (name "07. MANUFACTURER  PART NUMBER") "FDV303N")
        (field (name "13. CREATED DATE/NAME") "AUG 2018 / Hören")
      )
      (libsource (lib "SCT8-Board1") (part "FDV303N"))
    )
    (comp (ref "Q29")
      (value "Q")
      (footprint "SOT23-3")
      (description "MOSFET N-CH 25V 680MA SOT-23")
      (fields
        (field (name "02. DISTRIBUTOR PART NUMBER") "FDV303NDKR-ND")
        (field (name "07. MANUFACTURER  PART NUMBER") "FDV303N")
        (field (name "13. CREATED DATE/NAME") "AUG 2018 / Hören")
      )
      (libsource (lib "SCT8-Board1") (part "FDV303N"))
    )
    (comp (ref "Q30")
      (value "Q")
      (footprint "SOT23-3")
      (description "MOSFET N-CH 25V 680MA SOT-23")
      (fields
        (field (name "02. DISTRIBUTOR PART NUMBER") "FDV303NDKR-ND")
        (field (name "07. MANUFACTURER  PART NUMBER") "FDV303N")
        (field (name "13. CREATED DATE/NAME") "AUG 2018 / Hören")
      )
      (libsource (lib "SCT8-Board1") (part "FDV303N"))
    )
    (comp (ref "Q31")
      (value "Q")
      (footprint "SOT23-3")
      (description "MOSFET N-CH 25V 680MA SOT-23")
      (fields
        (field (name "02. DISTRIBUTOR PART NUMBER") "FDV303NDKR-ND")
        (field (name "07. MANUFACTURER  PART NUMBER") "FDV303N")
        (field (name "13. CREATED DATE/NAME") "AUG 2018 / Hören")
      )
      (libsource (lib "SCT8-Board1") (part "FDV303N"))
    )
    (comp (ref "Q32")
      (value "Q")
      (footprint "SOT23-3")
      (description "MOSFET N-CH 25V 680MA SOT-23")
      (fields
        (field (name "02. DISTRIBUTOR PART NUMBER") "FDV303NDKR-ND")
        (field (name "07. MANUFACTURER  PART NUMBER") "FDV303N")
        (field (name "13. CREATED DATE/NAME") "AUG 2018 / Hören")
      )
      (libsource (lib "SCT8-Board1") (part "FDV303N"))
    )
    (comp (ref "Q33")
      (value "Q")
      (footprint "SOT23-3")
      (description "MOSFET N-CH 25V 680MA SOT-23")
      (fields
        (field (name "02. DISTRIBUTOR PART NUMBER") "FDV303NDKR-ND")
        (field (name "07. MANUFACTURER  PART NUMBER") "FDV303N")
        (field (name "13. CREATED DATE/NAME") "AUG 2018 / Hören")
      )
      (libsource (lib "SCT8-Board1") (part "FDV303N"))
    )
    (comp (ref "Q34")
      (value "Q")
      (footprint "SOT23-3")
      (description "MOSFET N-CH 25V 680MA SOT-23")
      (fields
        (field (name "02. DISTRIBUTOR PART NUMBER") "FDV303NDKR-ND")
        (field (name "07. MANUFACTURER  PART NUMBER") "FDV303N")
        (field (name "13. CREATED DATE/NAME") "AUG 2018 / Hören")
      )
      (libsource (lib "SCT8-Board1") (part "FDV303N"))
    )
    (comp (ref "Q35")
      (value "Q")
      (footprint "SOT23-3")
      (description "MOSFET N-CH 25V 680MA SOT-23")
      (fields
        (field (name "02. DISTRIBUTOR PART NUMBER") "FDV303NDKR-ND")
        (field (name "07. MANUFACTURER  PART NUMBER") "FDV303N")
        (field (name "13. CREATED DATE/NAME") "AUG 2018 / Hören")
      )
      (libsource (lib "SCT8-Board1") (part "FDV303N"))
    )
    (comp (ref "Q36")
      (value "Q")
      (footprint "SOT23-3")
      (description "MOSFET N-CH 25V 680MA SOT-23")
      (fields
        (field (name "02. DISTRIBUTOR PART NUMBER") "FDV303NDKR-ND")
        (field (name "07. MANUFACTURER  PART NUMBER") "FDV303N")
        (field (name "13. CREATED DATE/NAME") "AUG 2018 / Hören")
      )
      (libsource (lib "SCT8-Board1") (part "FDV303N"))
    )
    (comp (ref "Q37")
      (value "Q")
      (footprint "SOT23-3")
      (description "MOSFET N-CH 25V 680MA SOT-23")
      (fields
        (field (name "02. DISTRIBUTOR PART NUMBER") "FDV303NDKR-ND")
        (field (name "07. MANUFACTURER  PART NUMBER") "FDV303N")
        (field (name "13. CREATED DATE/NAME") "AUG 2018 / Hören")
      )
      (libsource (lib "SCT8-Board1") (part "FDV303N"))
    )
    (comp (ref "Q38")
      (value "Q")
      (footprint "SOT23-3")
      (description "MOSFET N-CH 25V 680MA SOT-23")
      (fields
        (field (name "02. DISTRIBUTOR PART NUMBER") "FDV303NDKR-ND")
        (field (name "07. MANUFACTURER  PART NUMBER") "FDV303N")
        (field (name "13. CREATED DATE/NAME") "AUG 2018 / Hören")
      )
      (libsource (lib "SCT8-Board1") (part "FDV303N"))
    )
    (comp (ref "Q39")
      (value "Q")
      (footprint "SOT23-3")
      (description "MOSFET N-CH 25V 680MA SOT-23")
      (fields
        (field (name "02. DISTRIBUTOR PART NUMBER") "FDV303NDKR-ND")
        (field (name "07. MANUFACTURER  PART NUMBER") "FDV303N")
        (field (name "13. CREATED DATE/NAME") "AUG 2018 / Hören")
      )
      (libsource (lib "SCT8-Board1") (part "FDV303N"))
    )
    (comp (ref "Q40")
      (value "Q")
      (footprint "SOT23-3")
      (description "MOSFET N-CH 25V 680MA SOT-23")
      (fields
        (field (name "02. DISTRIBUTOR PART NUMBER") "FDV303NDKR-ND")
        (field (name "07. MANUFACTURER  PART NUMBER") "FDV303N")
        (field (name "13. CREATED DATE/NAME") "AUG 2018 / Hören")
      )
      (libsource (lib "SCT8-Board1") (part "FDV303N"))
    )
    (comp (ref "Q41")
      (value "Q")
      (footprint "SOT23-3")
      (description "MOSFET N-CH 25V 680MA SOT-23")
      (fields
        (field (name "02. DISTRIBUTOR PART NUMBER") "FDV303NDKR-ND")
        (field (name "07. MANUFACTURER  PART NUMBER") "FDV303N")
        (field (name "13. CREATED DATE/NAME") "AUG 2018 / Hören")
      )
      (libsource (lib "SCT8-Board1") (part "FDV303N"))
    )
    (comp (ref "Q42")
      (value "Q")
      (footprint "SOT23-3")
      (description "MOSFET N-CH 25V 680MA SOT-23")
      (fields
        (field (name "02. DISTRIBUTOR PART NUMBER") "FDV303NDKR-ND")
        (field (name "07. MANUFACTURER  PART NUMBER") "FDV303N")
        (field (name "13. CREATED DATE/NAME") "AUG 2018 / Hören")
      )
      (libsource (lib "SCT8-Board1") (part "FDV303N"))
    )
    (comp (ref "Q43")
      (value "Q")
      (footprint "SOT23-3")
      (description "MOSFET N-CH 25V 680MA SOT-23")
      (fields
        (field (name "02. DISTRIBUTOR PART NUMBER") "FDV303NDKR-ND")
        (field (name "07. MANUFACTURER  PART NUMBER") "FDV303N")
        (field (name "13. CREATED DATE/NAME") "AUG 2018 / Hören")
      )
      (libsource (lib "SCT8-Board1") (part "FDV303N"))
    )
    (comp (ref "Q44")
      (value "Q")
      (footprint "SOT23-3")
      (description "MOSFET N-CH 25V 680MA SOT-23")
      (fields
        (field (name "02. DISTRIBUTOR PART NUMBER") "FDV303NDKR-ND")
        (field (name "07. MANUFACTURER  PART NUMBER") "FDV303N")
        (field (name "13. CREATED DATE/NAME") "AUG 2018 / Hören")
      )
      (libsource (lib "SCT8-Board1") (part "FDV303N"))
    )
    (comp (ref "Q45")
      (value "Q")
      (footprint "SOT23-3")
      (description "MOSFET N-CH 25V 680MA SOT-23")
      (fields
        (field (name "02. DISTRIBUTOR PART NUMBER") "FDV303NDKR-ND")
        (field (name "07. MANUFACTURER  PART NUMBER") "FDV303N")
        (field (name "13. CREATED DATE/NAME") "AUG 2018 / Hören")
      )
      (libsource (lib "SCT8-Board1") (part "FDV303N"))
    )
    (comp (ref "Q46")
      (value "Q")
      (footprint "SOT23-3")
      (description "MOSFET N-CH 25V 680MA SOT-23")
      (fields
        (field (name "02. DISTRIBUTOR PART NUMBER") "FDV303NDKR-ND")
        (field (name "07. MANUFACTURER  PART NUMBER") "FDV303N")
        (field (name "13. CREATED DATE/NAME") "AUG 2018 / Hören")
      )
      (libsource (lib "SCT8-Board1") (part "FDV303N"))
    )
    (comp (ref "Q47")
      (value "Q")
      (footprint "SOT23-3")
      (description "MOSFET N-CH 25V 680MA SOT-23")
      (fields
        (field (name "02. DISTRIBUTOR PART NUMBER") "FDV303NDKR-ND")
        (field (name "07. MANUFACTURER  PART NUMBER") "FDV303N")
        (field (name "13. CREATED DATE/NAME") "AUG 2018 / Hören")
      )
      (libsource (lib "SCT8-Board1") (part "FDV303N"))
    )
    (comp (ref "Q48")
      (value "Q")
      (footprint "SOT23-3")
      (description "MOSFET N-CH 25V 680MA SOT-23")
      (fields
        (field (name "02. DISTRIBUTOR PART NUMBER") "FDV303NDKR-ND")
        (field (name "07. MANUFACTURER  PART NUMBER") "FDV303N")
        (field (name "13. CREATED DATE/NAME") "AUG 2018 / Hören")
      )
      (libsource (lib "SCT8-Board1") (part "FDV303N"))
    )
    (comp (ref "Q49")
      (value "Q")
      (footprint "SOT23-3")
      (description "MOSFET N-CH 25V 680MA SOT-23")
      (fields
        (field (name "02. DISTRIBUTOR PART NUMBER") "FDV303NDKR-ND")
        (field (name "07. MANUFACTURER  PART NUMBER") "FDV303N")
        (field (name "13. CREATED DATE/NAME") "AUG 2018 / Hören")
      )
      (libsource (lib "SCT8-Board1") (part "FDV303N"))
    )
    (comp (ref "Q50")
      (value "Q")
      (footprint "SOT23-3")
      (description "MOSFET N-CH 25V 680MA SOT-23")
      (fields
        (field (name "02. DISTRIBUTOR PART NUMBER") "FDV303NDKR-ND")
        (field (name "07. MANUFACTURER  PART NUMBER") "FDV303N")
        (field (name "13. CREATED DATE/NAME") "AUG 2018 / Hören")
      )
      (libsource (lib "SCT8-Board1") (part "FDV303N"))
    )
    (comp (ref "Q51")
      (value "Q")
      (footprint "SOT23-3")
      (description "MOSFET N-CH 25V 680MA SOT-23")
      (fields
        (field (name "02. DISTRIBUTOR PART NUMBER") "FDV303NDKR-ND")
        (field (name "07. MANUFACTURER  PART NUMBER") "FDV303N")
        (field (name "13. CREATED DATE/NAME") "AUG 2018 / Hören")
      )
      (libsource (lib "SCT8-Board1") (part "FDV303N"))
    )
    (comp (ref "Q52")
      (value "Q")
      (footprint "SOT23-3")
      (description "MOSFET N-CH 25V 680MA SOT-23")
      (fields
        (field (name "02. DISTRIBUTOR PART NUMBER") "FDV303NDKR-ND")
        (field (name "07. MANUFACTURER  PART NUMBER") "FDV303N")
        (field (name "13. CREATED DATE/NAME") "AUG 2018 / Hören")
      )
      (libsource (lib "SCT8-Board1") (part "FDV303N"))
    )
    (comp (ref "Q53")
      (value "Q")
      (footprint "SOT23-3")
      (description "MOSFET N-CH 25V 680MA SOT-23")
      (fields
        (field (name "02. DISTRIBUTOR PART NUMBER") "FDV303NDKR-ND")
        (field (name "07. MANUFACTURER  PART NUMBER") "FDV303N")
        (field (name "13. CREATED DATE/NAME") "AUG 2018 / Hören")
      )
      (libsource (lib "SCT8-Board1") (part "FDV303N"))
    )
    (comp (ref "Q54")
      (value "Q")
      (footprint "SOT23-3")
      (description "MOSFET N-CH 25V 680MA SOT-23")
      (fields
        (field (name "02. DISTRIBUTOR PART NUMBER") "FDV303NDKR-ND")
        (field (name "07. MANUFACTURER  PART NUMBER") "FDV303N")
        (field (name "13. CREATED DATE/NAME") "AUG 2018 / Hören")
      )
      (libsource (lib "SCT8-Board1") (part "FDV303N"))
    )
    (comp (ref "Q55")
      (value "Q")
      (footprint "SOT23-3")
      (description "MOSFET N-CH 25V 680MA SOT-23")
      (fields
        (field (name "02. DISTRIBUTOR PART NUMBER") "FDV303NDKR-ND")
        (field (name "07. MANUFACTURER  PART NUMBER") "FDV303N")
        (field (name "13. CREATED DATE/NAME") "AUG 2018 / Hören")
      )
      (libsource (lib "SCT8-Board1") (part "FDV303N"))
    )
    (comp (ref "Q56")
      (value "Q")
      (footprint "SOT23-3")
      (description "MOSFET N-CH 25V 680MA SOT-23")
      (fields
        (field (name "02. DISTRIBUTOR PART NUMBER") "FDV303NDKR-ND")
        (field (name "07. MANUFACTURER  PART NUMBER") "FDV303N")
        (field (name "13. CREATED DATE/NAME") "AUG 2018 / Hören")
      )
      (libsource (lib "SCT8-Board1") (part "FDV303N"))
    )
    (comp (ref "Q57")
      (value "Q")
      (footprint "SOT23-3")
      (description "MOSFET N-CH 25V 680MA SOT-23")
      (fields
        (field (name "02. DISTRIBUTOR PART NUMBER") "FDV303NDKR-ND")
        (field (name "07. MANUFACTURER  PART NUMBER") "FDV303N")
        (field (name "13. CREATED DATE/NAME") "AUG 2018 / Hören")
      )
      (libsource (lib "SCT8-Board1") (part "FDV303N"))
    )
    (comp (ref "Q58")
      (value "Q")
      (footprint "SOT23-3")
      (description "MOSFET N-CH 25V 680MA SOT-23")
      (fields
        (field (name "02. DISTRIBUTOR PART NUMBER") "FDV303NDKR-ND")
        (field (name "07. MANUFACTURER  PART NUMBER") "FDV303N")
        (field (name "13. CREATED DATE/NAME") "AUG 2018 / Hören")
      )
      (libsource (lib "SCT8-Board1") (part "FDV303N"))
    )
    (comp (ref "Q59")
      (value "Q")
      (footprint "SOT23-3")
      (description "MOSFET N-CH 25V 680MA SOT-23")
      (fields
        (field (name "02. DISTRIBUTOR PART NUMBER") "FDV303NDKR-ND")
        (field (name "07. MANUFACTURER  PART NUMBER") "FDV303N")
        (field (name "13. CREATED DATE/NAME") "AUG 2018 / Hören")
      )
      (libsource (lib "SCT8-Board1") (part "FDV303N"))
    )
    (comp (ref "Q60")
      (value "Q")
      (footprint "SOT23-3")
      (description "MOSFET N-CH 25V 680MA SOT-23")
      (fields
        (field (name "02. DISTRIBUTOR PART NUMBER") "FDV303NDKR-ND")
        (field (name "07. MANUFACTURER  PART NUMBER") "FDV303N")
        (field (name "13. CREATED DATE/NAME") "AUG 2018 / Hören")
      )
      (libsource (lib "SCT8-Board1") (part "FDV303N"))
    )
    (comp (ref "Q61")
      (value "Q")
      (footprint "SOT23-3")
      (description "MOSFET N-CH 25V 680MA SOT-23")
      (fields
        (field (name "02. DISTRIBUTOR PART NUMBER") "FDV303NDKR-ND")
        (field (name "07. MANUFACTURER  PART NUMBER") "FDV303N")
        (field (name "13. CREATED DATE/NAME") "AUG 2018 / Hören")
      )
      (libsource (lib "SCT8-Board1") (part "FDV303N"))
    )
    (comp (ref "Q62")
      (value "Q")
      (footprint "SOT23-3")
      (description "MOSFET N-CH 25V 680MA SOT-23")
      (fields
        (field (name "02. DISTRIBUTOR PART NUMBER") "FDV303NDKR-ND")
        (field (name "07. MANUFACTURER  PART NUMBER") "FDV303N")
        (field (name "13. CREATED DATE/NAME") "AUG 2018 / Hören")
      )
      (libsource (lib "SCT8-Board1") (part "FDV303N"))
    )
    (comp (ref "Q63")
      (value "Q")
      (footprint "SOT23-3")
      (description "MOSFET N-CH 25V 680MA SOT-23")
      (fields
        (field (name "02. DISTRIBUTOR PART NUMBER") "FDV303NDKR-ND")
        (field (name "07. MANUFACTURER  PART NUMBER") "FDV303N")
        (field (name "13. CREATED DATE/NAME") "AUG 2018 / Hören")
      )
      (libsource (lib "SCT8-Board1") (part "FDV303N"))
    )
    (comp (ref "Q64")
      (value "Q")
      (footprint "SOT23-3")
      (description "MOSFET N-CH 25V 680MA SOT-23")
      (fields
        (field (name "02. DISTRIBUTOR PART NUMBER") "FDV303NDKR-ND")
        (field (name "07. MANUFACTURER  PART NUMBER") "FDV303N")
        (field (name "13. CREATED DATE/NAME") "AUG 2018 / Hören")
      )
      (libsource (lib "SCT8-Board1") (part "FDV303N"))
    )
    (comp (ref "R1")
      (value "4K7")
      (footprint "R0402 Reflow")
      (description "RES SMD 4.7K OHM 1% 1/16W 0402")
      (fields
        (field (name "TOLERANCE") "±1%")
        (field (name "02. DISTRIBUTOR PART NUMBER") "311-4.7KLRDKR-ND")
        (field (name "13. CREATED DATE/NAME") "AUG2018/Hören")
      )
      (libsource (lib "chickenfood") (part "R"))
    )
    (comp (ref "R2")
      (value "4K7")
      (footprint "R0402 Reflow")
      (description "RES SMD 4.7K OHM 1% 1/16W 0402")
      (fields
        (field (name "TOLERANCE") "±1%")
        (field (name "02. DISTRIBUTOR PART NUMBER") "311-4.7KLRDKR-ND")
        (field (name "13. CREATED DATE/NAME") "AUG2018/Hören")
      )
      (libsource (lib "chickenfood") (part "R"))
    )
    (comp (ref "R3")
      (value "4K7")
      (footprint "R0402 Reflow")
      (description "RES SMD 4.7K OHM 1% 1/16W 0402")
      (fields
        (field (name "TOLERANCE") "±1%")
        (field (name "02. DISTRIBUTOR PART NUMBER") "311-4.7KLRDKR-ND")
        (field (name "13. CREATED DATE/NAME") "AUG2018/Hören")
      )
      (libsource (lib "chickenfood") (part "R"))
    )
    (comp (ref "R4")
      (value "4K7")
      (footprint "R0402 Reflow")
      (description "RES SMD 4.7K OHM 1% 1/16W 0402")
      (fields
        (field (name "TOLERANCE") "±1%")
        (field (name "02. DISTRIBUTOR PART NUMBER") "311-4.7KLRDKR-ND")
        (field (name "13. CREATED DATE/NAME") "AUG2018/Hören")
      )
      (libsource (lib "chickenfood") (part "R"))
    )
    (comp (ref "R5")
      (value "4K7")
      (footprint "R0402 Reflow")
      (description "RES SMD 4.7K OHM 1% 1/16W 0402")
      (fields
        (field (name "TOLERANCE") "±1%")
        (field (name "02. DISTRIBUTOR PART NUMBER") "311-4.7KLRDKR-ND")
        (field (name "13. CREATED DATE/NAME") "AUG2018/Hören")
      )
      (libsource (lib "chickenfood") (part "R"))
    )
    (comp (ref "R6")
      (value "4K7")
      (footprint "R0402 Reflow")
      (description "RES SMD 4.7K OHM 1% 1/16W 0402")
      (fields
        (field (name "TOLERANCE") "±1%")
        (field (name "02. DISTRIBUTOR PART NUMBER") "311-4.7KLRDKR-ND")
        (field (name "13. CREATED DATE/NAME") "AUG2018/Hören")
      )
      (libsource (lib "chickenfood") (part "R"))
    )
    (comp (ref "R7")
      (value "4K7")
      (footprint "R0402 Reflow")
      (description "RES SMD 4.7K OHM 1% 1/16W 0402")
      (fields
        (field (name "TOLERANCE") "±1%")
        (field (name "02. DISTRIBUTOR PART NUMBER") "311-4.7KLRDKR-ND")
        (field (name "13. CREATED DATE/NAME") "AUG2018/Hören")
      )
      (libsource (lib "chickenfood") (part "R"))
    )
    (comp (ref "R8")
      (value "4K7")
      (footprint "R0402 Reflow")
      (description "RES SMD 4.7K OHM 1% 1/16W 0402")
      (fields
        (field (name "TOLERANCE") "±1%")
        (field (name "02. DISTRIBUTOR PART NUMBER") "311-4.7KLRDKR-ND")
        (field (name "13. CREATED DATE/NAME") "AUG2018/Hören")
      )
      (libsource (lib "chickenfood") (part "R"))
    )
    (comp (ref "R9")
      (value "4K7")
      (footprint "R0402 Reflow")
      (description "RES SMD 4.7K OHM 1% 1/16W 0402")
      (fields
        (field (name "TOLERANCE") "±1%")
        (field (name "02. DISTRIBUTOR PART NUMBER") "311-4.7KLRDKR-ND")
        (field (name "13. CREATED DATE/NAME") "AUG2018/Hören")
      )
      (libsource (lib "chickenfood") (part "R"))
    )
    (comp (ref "R10")
      (value "4K7")
      (footprint "R0402 Reflow")
      (description "RES SMD 4.7K OHM 1% 1/16W 0402")
      (fields
        (field (name "TOLERANCE") "±1%")
        (field (name "02. DISTRIBUTOR PART NUMBER") "311-4.7KLRDKR-ND")
        (field (name "13. CREATED DATE/NAME") "AUG2018/Hören")
      )
      (libsource (lib "chickenfood") (part "R"))
    )
    (comp (ref "R11")
      (value "4K7")
      (footprint "R0402 Reflow")
      (description "RES SMD 4.7K OHM 1% 1/16W 0402")
      (fields
        (field (name "TOLERANCE") "±1%")
        (field (name "02. DISTRIBUTOR PART NUMBER") "311-4.7KLRDKR-ND")
        (field (name "13. CREATED DATE/NAME") "AUG2018/Hören")
      )
      (libsource (lib "chickenfood") (part "R"))
    )
    (comp (ref "R12")
      (value "4K7")
      (footprint "R0402 Reflow")
      (description "RES SMD 4.7K OHM 1% 1/16W 0402")
      (fields
        (field (name "TOLERANCE") "±1%")
        (field (name "02. DISTRIBUTOR PART NUMBER") "311-4.7KLRDKR-ND")
        (field (name "13. CREATED DATE/NAME") "AUG2018/Hören")
      )
      (libsource (lib "chickenfood") (part "R"))
    )
    (comp (ref "R13")
      (value "4K7")
      (footprint "R0402 Reflow")
      (description "RES SMD 4.7K OHM 1% 1/16W 0402")
      (fields
        (field (name "TOLERANCE") "±1%")
        (field (name "02. DISTRIBUTOR PART NUMBER") "311-4.7KLRDKR-ND")
        (field (name "13. CREATED DATE/NAME") "AUG2018/Hören")
      )
      (libsource (lib "chickenfood") (part "R"))
    )
    (comp (ref "R14")
      (value "4K7")
      (footprint "R0402 Reflow")
      (description "RES SMD 4.7K OHM 1% 1/16W 0402")
      (fields
        (field (name "TOLERANCE") "±1%")
        (field (name "02. DISTRIBUTOR PART NUMBER") "311-4.7KLRDKR-ND")
        (field (name "13. CREATED DATE/NAME") "AUG2018/Hören")
      )
      (libsource (lib "chickenfood") (part "R"))
    )
    (comp (ref "R15")
      (value "4K7")
      (footprint "R0402 Reflow")
      (description "RES SMD 4.7K OHM 1% 1/16W 0402")
      (fields
        (field (name "TOLERANCE") "±1%")
        (field (name "02. DISTRIBUTOR PART NUMBER") "311-4.7KLRDKR-ND")
        (field (name "13. CREATED DATE/NAME") "AUG2018/Hören")
      )
      (libsource (lib "chickenfood") (part "R"))
    )
    (comp (ref "R16")
      (value "4K7")
      (footprint "R0402 Reflow")
      (description "RES SMD 4.7K OHM 1% 1/16W 0402")
      (fields
        (field (name "TOLERANCE") "±1%")
        (field (name "02. DISTRIBUTOR PART NUMBER") "311-4.7KLRDKR-ND")
        (field (name "13. CREATED DATE/NAME") "AUG2018/Hören")
      )
      (libsource (lib "chickenfood") (part "R"))
    )
    (comp (ref "R17")
      (value "4K7")
      (footprint "R0402 Reflow")
      (description "RES SMD 4.7K OHM 1% 1/16W 0402")
      (fields
        (field (name "TOLERANCE") "±1%")
        (field (name "02. DISTRIBUTOR PART NUMBER") "311-4.7KLRDKR-ND")
        (field (name "13. CREATED DATE/NAME") "AUG2018/Hören")
      )
      (libsource (lib "chickenfood") (part "R"))
    )
    (comp (ref "R18")
      (value "4K7")
      (footprint "R0402 Reflow")
      (description "RES SMD 4.7K OHM 1% 1/16W 0402")
      (fields
        (field (name "TOLERANCE") "±1%")
        (field (name "02. DISTRIBUTOR PART NUMBER") "311-4.7KLRDKR-ND")
        (field (name "13. CREATED DATE/NAME") "AUG2018/Hören")
      )
      (libsource (lib "chickenfood") (part "R"))
    )
    (comp (ref "R19")
      (value "4K7")
      (footprint "R0402 Reflow")
      (description "RES SMD 4.7K OHM 1% 1/16W 0402")
      (fields
        (field (name "TOLERANCE") "±1%")
        (field (name "02. DISTRIBUTOR PART NUMBER") "311-4.7KLRDKR-ND")
        (field (name "13. CREATED DATE/NAME") "AUG2018/Hören")
      )
      (libsource (lib "chickenfood") (part "R"))
    )
    (comp (ref "R20")
      (value "4K7")
      (footprint "R0402 Reflow")
      (description "RES SMD 4.7K OHM 1% 1/16W 0402")
      (fields
        (field (name "TOLERANCE") "±1%")
        (field (name "02. DISTRIBUTOR PART NUMBER") "311-4.7KLRDKR-ND")
        (field (name "13. CREATED DATE/NAME") "AUG2018/Hören")
      )
      (libsource (lib "chickenfood") (part "R"))
    )
    (comp (ref "R21")
      (value "4K7")
      (footprint "R0402 Reflow")
      (description "RES SMD 4.7K OHM 1% 1/16W 0402")
      (fields
        (field (name "TOLERANCE") "±1%")
        (field (name "02. DISTRIBUTOR PART NUMBER") "311-4.7KLRDKR-ND")
        (field (name "13. CREATED DATE/NAME") "AUG2018/Hören")
      )
      (libsource (lib "chickenfood") (part "R"))
    )
    (comp (ref "R22")
      (value "4K7")
      (footprint "R0402 Reflow")
      (description "RES SMD 4.7K OHM 1% 1/16W 0402")
      (fields
        (field (name "TOLERANCE") "±1%")
        (field (name "02. DISTRIBUTOR PART NUMBER") "311-4.7KLRDKR-ND")
        (field (name "13. CREATED DATE/NAME") "AUG2018/Hören")
      )
      (libsource (lib "chickenfood") (part "R"))
    )
    (comp (ref "R23")
      (value "4K7")
      (footprint "R0402 Reflow")
      (description "RES SMD 4.7K OHM 1% 1/16W 0402")
      (fields
        (field (name "TOLERANCE") "±1%")
        (field (name "02. DISTRIBUTOR PART NUMBER") "311-4.7KLRDKR-ND")
        (field (name "13. CREATED DATE/NAME") "AUG2018/Hören")
      )
      (libsource (lib "chickenfood") (part "R"))
    )
    (comp (ref "R24")
      (value "4K7")
      (footprint "R0402 Reflow")
      (description "RES SMD 4.7K OHM 1% 1/16W 0402")
      (fields
        (field (name "TOLERANCE") "±1%")
        (field (name "02. DISTRIBUTOR PART NUMBER") "311-4.7KLRDKR-ND")
        (field (name "13. CREATED DATE/NAME") "AUG2018/Hören")
      )
      (libsource (lib "chickenfood") (part "R"))
    )
    (comp (ref "R25")
      (value "4K7")
      (footprint "R0402 Reflow")
      (description "RES SMD 4.7K OHM 1% 1/16W 0402")
      (fields
        (field (name "TOLERANCE") "±1%")
        (field (name "02. DISTRIBUTOR PART NUMBER") "311-4.7KLRDKR-ND")
        (field (name "13. CREATED DATE/NAME") "AUG2018/Hören")
      )
      (libsource (lib "chickenfood") (part "R"))
    )
    (comp (ref "R26")
      (value "4K7")
      (footprint "R0402 Reflow")
      (description "RES SMD 4.7K OHM 1% 1/16W 0402")
      (fields
        (field (name "TOLERANCE") "±1%")
        (field (name "02. DISTRIBUTOR PART NUMBER") "311-4.7KLRDKR-ND")
        (field (name "13. CREATED DATE/NAME") "AUG2018/Hören")
      )
      (libsource (lib "chickenfood") (part "R"))
    )
    (comp (ref "R27")
      (value "4K7")
      (footprint "R0402 Reflow")
      (description "RES SMD 4.7K OHM 1% 1/16W 0402")
      (fields
        (field (name "TOLERANCE") "±1%")
        (field (name "02. DISTRIBUTOR PART NUMBER") "311-4.7KLRDKR-ND")
        (field (name "13. CREATED DATE/NAME") "AUG2018/Hören")
      )
      (libsource (lib "chickenfood") (part "R"))
    )
    (comp (ref "R28")
      (value "4K7")
      (footprint "R0402 Reflow")
      (description "RES SMD 4.7K OHM 1% 1/16W 0402")
      (fields
        (field (name "TOLERANCE") "±1%")
        (field (name "02. DISTRIBUTOR PART NUMBER") "311-4.7KLRDKR-ND")
        (field (name "13. CREATED DATE/NAME") "AUG2018/Hören")
      )
      (libsource (lib "chickenfood") (part "R"))
    )
    (comp (ref "R29")
      (value "4K7")
      (footprint "R0402 Reflow")
      (description "RES SMD 4.7K OHM 1% 1/16W 0402")
      (fields
        (field (name "TOLERANCE") "±1%")
        (field (name "02. DISTRIBUTOR PART NUMBER") "311-4.7KLRDKR-ND")
        (field (name "13. CREATED DATE/NAME") "AUG2018/Hören")
      )
      (libsource (lib "chickenfood") (part "R"))
    )
    (comp (ref "R30")
      (value "4K7")
      (footprint "R0402 Reflow")
      (description "RES SMD 4.7K OHM 1% 1/16W 0402")
      (fields
        (field (name "TOLERANCE") "±1%")
        (field (name "02. DISTRIBUTOR PART NUMBER") "311-4.7KLRDKR-ND")
        (field (name "13. CREATED DATE/NAME") "AUG2018/Hören")
      )
      (libsource (lib "chickenfood") (part "R"))
    )
    (comp (ref "R31")
      (value "4K7")
      (footprint "R0402 Reflow")
      (description "RES SMD 4.7K OHM 1% 1/16W 0402")
      (fields
        (field (name "TOLERANCE") "±1%")
        (field (name "02. DISTRIBUTOR PART NUMBER") "311-4.7KLRDKR-ND")
        (field (name "13. CREATED DATE/NAME") "AUG2018/Hören")
      )
      (libsource (lib "chickenfood") (part "R"))
    )
    (comp (ref "R32")
      (value "4K7")
      (footprint "R0402 Reflow")
      (description "RES SMD 4.7K OHM 1% 1/16W 0402")
      (fields
        (field (name "TOLERANCE") "±1%")
        (field (name "02. DISTRIBUTOR PART NUMBER") "311-4.7KLRDKR-ND")
        (field (name "13. CREATED DATE/NAME") "AUG2018/Hören")
      )
      (libsource (lib "chickenfood") (part "R"))
    )
    (comp (ref "R33")
      (value "4K7")
      (footprint "R0402 Reflow")
      (description "RES SMD 4.7K OHM 1% 1/16W 0402")
      (fields
        (field (name "TOLERANCE") "±1%")
        (field (name "02. DISTRIBUTOR PART NUMBER") "311-4.7KLRDKR-ND")
        (field (name "13. CREATED DATE/NAME") "AUG2018/Hören")
      )
      (libsource (lib "chickenfood") (part "R"))
    )
    (comp (ref "R34")
      (value "4K7")
      (footprint "R0402 Reflow")
      (description "RES SMD 4.7K OHM 1% 1/16W 0402")
      (fields
        (field (name "TOLERANCE") "±1%")
        (field (name "02. DISTRIBUTOR PART NUMBER") "311-4.7KLRDKR-ND")
        (field (name "13. CREATED DATE/NAME") "AUG2018/Hören")
      )
      (libsource (lib "chickenfood") (part "R"))
    )
    (comp (ref "R35")
      (value "4K7")
      (footprint "R0402 Reflow")
      (description "RES SMD 4.7K OHM 1% 1/16W 0402")
      (fields
        (field (name "TOLERANCE") "±1%")
        (field (name "02. DISTRIBUTOR PART NUMBER") "311-4.7KLRDKR-ND")
        (field (name "13. CREATED DATE/NAME") "AUG2018/Hören")
      )
      (libsource (lib "chickenfood") (part "R"))
    )
    (comp (ref "R36")
      (value "4K7")
      (footprint "R0402 Reflow")
      (description "RES SMD 4.7K OHM 1% 1/16W 0402")
      (fields
        (field (name "TOLERANCE") "±1%")
        (field (name "02. DISTRIBUTOR PART NUMBER") "311-4.7KLRDKR-ND")
        (field (name "13. CREATED DATE/NAME") "AUG2018/Hören")
      )
      (libsource (lib "chickenfood") (part "R"))
    )
    (comp (ref "R37")
      (value "4K7")
      (footprint "R0402 Reflow")
      (description "RES SMD 4.7K OHM 1% 1/16W 0402")
      (fields
        (field (name "TOLERANCE") "±1%")
        (field (name "02. DISTRIBUTOR PART NUMBER") "311-4.7KLRDKR-ND")
        (field (name "13. CREATED DATE/NAME") "AUG2018/Hören")
      )
      (libsource (lib "chickenfood") (part "R"))
    )
    (comp (ref "R38")
      (value "4K7")
      (footprint "R0402 Reflow")
      (description "RES SMD 4.7K OHM 1% 1/16W 0402")
      (fields
        (field (name "TOLERANCE") "±1%")
        (field (name "02. DISTRIBUTOR PART NUMBER") "311-4.7KLRDKR-ND")
        (field (name "13. CREATED DATE/NAME") "AUG2018/Hören")
      )
      (libsource (lib "chickenfood") (part "R"))
    )
    (comp (ref "R39")
      (value "4K7")
      (footprint "R0402 Reflow")
      (description "RES SMD 4.7K OHM 1% 1/16W 0402")
      (fields
        (field (name "TOLERANCE") "±1%")
        (field (name "02. DISTRIBUTOR PART NUMBER") "311-4.7KLRDKR-ND")
        (field (name "13. CREATED DATE/NAME") "AUG2018/Hören")
      )
      (libsource (lib "chickenfood") (part "R"))
    )
    (comp (ref "R40")
      (value "4K7")
      (footprint "R0402 Reflow")
      (description "RES SMD 4.7K OHM 1% 1/16W 0402")
      (fields
        (field (name "TOLERANCE") "±1%")
        (field (name "02. DISTRIBUTOR PART NUMBER") "311-4.7KLRDKR-ND")
        (field (name "13. CREATED DATE/NAME") "AUG2018/Hören")
      )
      (libsource (lib "chickenfood") (part "R"))
    )
    (comp (ref "R41")
      (value "4K7")
      (footprint "R0402 Reflow")
      (description "RES SMD 4.7K OHM 1% 1/16W 0402")
      (fields
        (field (name "TOLERANCE") "±1%")
        (field (name "02. DISTRIBUTOR PART NUMBER") "311-4.7KLRDKR-ND")
        (field (name "13. CREATED DATE/NAME") "AUG2018/Hören")
      )
      (libsource (lib "chickenfood") (part "R"))
    )
    (comp (ref "R42")
      (value "4K7")
      (footprint "R0402 Reflow")
      (description "RES SMD 4.7K OHM 1% 1/16W 0402")
      (fields
        (field (name "TOLERANCE") "±1%")
        (field (name "02. DISTRIBUTOR PART NUMBER") "311-4.7KLRDKR-ND")
        (field (name "13. CREATED DATE/NAME") "AUG2018/Hören")
      )
      (libsource (lib "chickenfood") (part "R"))
    )
    (comp (ref "R48")
      (value "4K7")
      (footprint "R0402 Reflow")
      (description "RES SMD 4.7K OHM 1% 1/16W 0402")
      (fields
        (field (name "TOLERANCE") "±1%")
        (field (name "02. DISTRIBUTOR PART NUMBER") "311-4.7KLRDKR-ND")
        (field (name "13. CREATED DATE/NAME") "AUG2018/Hören")
      )
      (libsource (lib "chickenfood") (part "R"))
    )
    (comp (ref "R49")
      (value "4K7")
      (footprint "R0402 Reflow")
      (description "RES SMD 4.7K OHM 1% 1/16W 0402")
      (fields
        (field (name "TOLERANCE") "±1%")
        (field (name "02. DISTRIBUTOR PART NUMBER") "311-4.7KLRDKR-ND")
        (field (name "13. CREATED DATE/NAME") "AUG2018/Hören")
      )
      (libsource (lib "chickenfood") (part "R"))
    )
    (comp (ref "R50")
      (value "4K7")
      (footprint "R0402 Reflow")
      (description "RES SMD 4.7K OHM 1% 1/16W 0402")
      (fields
        (field (name "TOLERANCE") "±1%")
        (field (name "02. DISTRIBUTOR PART NUMBER") "311-4.7KLRDKR-ND")
        (field (name "13. CREATED DATE/NAME") "AUG2018/Hören")
      )
      (libsource (lib "chickenfood") (part "R"))
    )
    (comp (ref "R51")
      (value "4K7")
      (footprint "R0402 Reflow")
      (description "RES SMD 4.7K OHM 1% 1/16W 0402")
      (fields
        (field (name "TOLERANCE") "±1%")
        (field (name "02. DISTRIBUTOR PART NUMBER") "311-4.7KLRDKR-ND")
        (field (name "13. CREATED DATE/NAME") "AUG2018/Hören")
      )
      (libsource (lib "chickenfood") (part "R"))
    )
    (comp (ref "R52")
      (value "4K7")
      (footprint "R0402 Reflow")
      (description "RES SMD 4.7K OHM 1% 1/16W 0402")
      (fields
        (field (name "TOLERANCE") "±1%")
        (field (name "02. DISTRIBUTOR PART NUMBER") "311-4.7KLRDKR-ND")
        (field (name "13. CREATED DATE/NAME") "AUG2018/Hören")
      )
      (libsource (lib "chickenfood") (part "R"))
    )
    (comp (ref "R53")
      (value "4K7")
      (footprint "R0402 Reflow")
      (description "RES SMD 4.7K OHM 1% 1/16W 0402")
      (fields
        (field (name "TOLERANCE") "±1%")
        (field (name "02. DISTRIBUTOR PART NUMBER") "311-4.7KLRDKR-ND")
        (field (name "13. CREATED DATE/NAME") "AUG2018/Hören")
      )
      (libsource (lib "chickenfood") (part "R"))
    )
    (comp (ref "R54")
      (value "4K7")
      (footprint "R0402 Reflow")
      (description "RES SMD 4.7K OHM 1% 1/16W 0402")
      (fields
        (field (name "TOLERANCE") "±1%")
        (field (name "02. DISTRIBUTOR PART NUMBER") "311-4.7KLRDKR-ND")
        (field (name "13. CREATED DATE/NAME") "AUG2018/Hören")
      )
      (libsource (lib "chickenfood") (part "R"))
    )
    (comp (ref "R55")
      (value "4K7")
      (footprint "R0402 Reflow")
      (description "RES SMD 4.7K OHM 1% 1/16W 0402")
      (fields
        (field (name "TOLERANCE") "±1%")
        (field (name "02. DISTRIBUTOR PART NUMBER") "311-4.7KLRDKR-ND")
        (field (name "13. CREATED DATE/NAME") "AUG2018/Hören")
      )
      (libsource (lib "chickenfood") (part "R"))
    )
    (comp (ref "R56")
      (value "4K7")
      (footprint "R0402 Reflow")
      (description "RES SMD 4.7K OHM 1% 1/16W 0402")
      (fields
        (field (name "TOLERANCE") "±1%")
        (field (name "02. DISTRIBUTOR PART NUMBER") "311-4.7KLRDKR-ND")
        (field (name "13. CREATED DATE/NAME") "AUG2018/Hören")
      )
      (libsource (lib "chickenfood") (part "R"))
    )
    (comp (ref "R57")
      (value "4K7")
      (footprint "R0402 Reflow")
      (description "RES SMD 4.7K OHM 1% 1/16W 0402")
      (fields
        (field (name "TOLERANCE") "±1%")
        (field (name "02. DISTRIBUTOR PART NUMBER") "311-4.7KLRDKR-ND")
        (field (name "13. CREATED DATE/NAME") "AUG2018/Hören")
      )
      (libsource (lib "chickenfood") (part "R"))
    )
    (comp (ref "R58")
      (value "4K7")
      (footprint "R0402 Reflow")
      (description "RES SMD 4.7K OHM 1% 1/16W 0402")
      (fields
        (field (name "TOLERANCE") "±1%")
        (field (name "02. DISTRIBUTOR PART NUMBER") "311-4.7KLRDKR-ND")
        (field (name "13. CREATED DATE/NAME") "AUG2018/Hören")
      )
      (libsource (lib "chickenfood") (part "R"))
    )
    (comp (ref "R59")
      (value "4K7")
      (footprint "R0402 Reflow")
      (description "RES SMD 4.7K OHM 1% 1/16W 0402")
      (fields
        (field (name "TOLERANCE") "±1%")
        (field (name "02. DISTRIBUTOR PART NUMBER") "311-4.7KLRDKR-ND")
        (field (name "13. CREATED DATE/NAME") "AUG2018/Hören")
      )
      (libsource (lib "chickenfood") (part "R"))
    )
    (comp (ref "R60")
      (value "4K7")
      (footprint "R0402 Reflow")
      (description "RES SMD 4.7K OHM 1% 1/16W 0402")
      (fields
        (field (name "TOLERANCE") "±1%")
        (field (name "02. DISTRIBUTOR PART NUMBER") "311-4.7KLRDKR-ND")
        (field (name "13. CREATED DATE/NAME") "AUG2018/Hören")
      )
      (libsource (lib "chickenfood") (part "R"))
    )
    (comp (ref "R61")
      (value "4K7")
      (footprint "R0402 Reflow")
      (description "RES SMD 4.7K OHM 1% 1/16W 0402")
      (fields
        (field (name "TOLERANCE") "±1%")
        (field (name "02. DISTRIBUTOR PART NUMBER") "311-4.7KLRDKR-ND")
        (field (name "13. CREATED DATE/NAME") "AUG2018/Hören")
      )
      (libsource (lib "chickenfood") (part "R"))
    )
    (comp (ref "R62")
      (value "4K7")
      (footprint "R0402 Reflow")
      (description "RES SMD 4.7K OHM 1% 1/16W 0402")
      (fields
        (field (name "TOLERANCE") "±1%")
        (field (name "02. DISTRIBUTOR PART NUMBER") "311-4.7KLRDKR-ND")
        (field (name "13. CREATED DATE/NAME") "AUG2018/Hören")
      )
      (libsource (lib "chickenfood") (part "R"))
    )
    (comp (ref "R63")
      (value "4K7")
      (footprint "R0402 Reflow")
      (description "RES SMD 4.7K OHM 1% 1/16W 0402")
      (fields
        (field (name "TOLERANCE") "±1%")
        (field (name "02. DISTRIBUTOR PART NUMBER") "311-4.7KLRDKR-ND")
        (field (name "13. CREATED DATE/NAME") "AUG2018/Hören")
      )
      (libsource (lib "chickenfood") (part "R"))
    )
    (comp (ref "R64")
      (value "4K7")
      (footprint "R0402 Reflow")
      (description "RES SMD 4.7K OHM 1% 1/16W 0402")
      (fields
        (field (name "TOLERANCE") "±1%")
        (field (name "02. DISTRIBUTOR PART NUMBER") "311-4.7KLRDKR-ND")
        (field (name "13. CREATED DATE/NAME") "AUG2018/Hören")
      )
      (libsource (lib "chickenfood") (part "R"))
    )
    (comp (ref "R65")
      (value "4K7")
      (footprint "R0402 Reflow")
      (description "RES SMD 4.7K OHM 1% 1/16W 0402")
      (fields
        (field (name "TOLERANCE") "±1%")
        (field (name "02. DISTRIBUTOR PART NUMBER") "311-4.7KLRDKR-ND")
        (field (name "13. CREATED DATE/NAME") "AUG2018/Hören")
      )
      (libsource (lib "chickenfood") (part "R"))
    )
    (comp (ref "R66")
      (value "4K7")
      (footprint "R0402 Reflow")
      (description "RES SMD 4.7K OHM 1% 1/16W 0402")
      (fields
        (field (name "TOLERANCE") "±1%")
        (field (name "02. DISTRIBUTOR PART NUMBER") "311-4.7KLRDKR-ND")
        (field (name "13. CREATED DATE/NAME") "AUG2018/Hören")
      )
      (libsource (lib "chickenfood") (part "R"))
    )
    (comp (ref "R67")
      (value "4K7")
      (footprint "R0402 Reflow")
      (description "RES SMD 4.7K OHM 1% 1/16W 0402")
      (fields
        (field (name "TOLERANCE") "±1%")
        (field (name "02. DISTRIBUTOR PART NUMBER") "311-4.7KLRDKR-ND")
        (field (name "13. CREATED DATE/NAME") "AUG2018/Hören")
      )
      (libsource (lib "chickenfood") (part "R"))
    )
    (comp (ref "R68")
      (value "4K7")
      (footprint "R0402 Reflow")
      (description "RES SMD 4.7K OHM 1% 1/16W 0402")
      (fields
        (field (name "TOLERANCE") "±1%")
        (field (name "02. DISTRIBUTOR PART NUMBER") "311-4.7KLRDKR-ND")
        (field (name "13. CREATED DATE/NAME") "AUG2018/Hören")
      )
      (libsource (lib "chickenfood") (part "R"))
    )
    (comp (ref "R69")
      (value "4K7")
      (footprint "R0402 Reflow")
      (description "RES SMD 4.7K OHM 1% 1/16W 0402")
      (fields
        (field (name "TOLERANCE") "±1%")
        (field (name "02. DISTRIBUTOR PART NUMBER") "311-4.7KLRDKR-ND")
        (field (name "13. CREATED DATE/NAME") "AUG2018/Hören")
      )
      (libsource (lib "chickenfood") (part "R"))
    )
    (comp (ref "R121")
      (value "10k")
      (footprint "R0402 Reflow")
      (description "RES SMD 10K OHM 1% 1/16W 0402")
      (fields
        (field (name "TOLERANCE") "±1%")
        (field (name "02. DISTRIBUTOR PART NUMBER") "311-10.0KLRDKR-ND")
        (field (name "13. CREATED DATE/NAME") "AUG2018/Hören")
      )
      (libsource (lib "chickenfood") (part "R"))
    )
    (comp (ref "R125")
      (value "3k6")
      (footprint "R0603 Reflow")
      (description "RES SMD 3.6K OHM 1% 1/10W 0603")
      (fields
        (field (name "TOLERANCE") "±1%")
        (field (name "02. DISTRIBUTOR PART NUMBER") "311-3.60KHRCT-ND")
        (field (name "13. CREATED DATE/NAME") "AUG2018/Hören")
      )
      (libsource (lib "chickenfood") (part "R"))
    )
    (comp (ref "TP5")
      (value "TP")
      (footprint "DualTestpoint 100mils")
      (description "Dual testpoint, pitch 2.54mm")
      (fields
        (field (name "02. DISTRIBUTOR PART NUMBER") "HMTSW-103-07-G-S-240")
        (field (name "13. CREATED DATE/NAME") "AUG2018/Hören")
      )
      (libsource (lib "PCB-Tester-Board-V1") (part "DualTestpoint 100mils"))
    )
    (comp (ref "TP6")
      (value "TP")
      (footprint "DualTestpoint 100mils")
      (description "Dual testpoint, pitch 2.54mm")
      (fields
        (field (name "02. DISTRIBUTOR PART NUMBER") "HMTSW-103-07-G-S-240")
        (field (name "13. CREATED DATE/NAME") "AUG2018/Hören")
      )
      (libsource (lib "PCB-Tester-Board-V1") (part "DualTestpoint 100mils"))
    )
    (comp (ref "X1")
      (value "X")
      (description "32 x 2 x 1.27mm SOCKET DISCRETE CABL COLORED")
      (fields
        (field (name "02. DISTRIBUTOR PART NUMBER") "SFSD-32-30C-G-15.00-S")
        (field (name "13. CREATED DATE/NAME") "??? / Hören")
      )
      (libsource (lib "PCB-Relay-Board-V1") (part "SFSD-32-30C-G-15.00-S"))
    )
    (comp (ref "X2")
      (value "X")
      (footprint "TFC-132-01-F-D-RA")
      (description "CONN HEADER TH RA 48POS 1.27MM")
      (fields
        (field (name "02. DISTRIBUTOR PART NUMBER") "TFC-132-01-F-D-RA")
        (field (name "13. CREATED DATE/NAME") "??? / Hören")
      )
      (libsource (lib "PCB-Relay-Board-V1") (part "TFC-132-01-F-D-RA"))
    )
    (comp (ref "X3")
      (value "X")
      (footprint "CONFIG64")
      (description "PCB Tester Configuration Matrix for 48 Relays over 8 ABUSes")
      (fields (field (name "13. CREATED DATE/NAME") "??? / Hören"))
      (libsource (lib "PCB-Relay-Board-V1") (part "CONFIG64"))
    )
    (comp (ref "X4")
      (value "X")
      (footprint "PCIE-036-02-F-D-Fingers")
      (description "CONN PCI Card Edge 36POS")
      (libsource (lib "Connectors") (part "PCIE-036-02-F-D-Fingers"))
    )
  )
  (nets
    (net (code "4") (name "/A0") (class "Default")
      (node (ref "X4") (pin "B18") (pinfunction "B18_B18") (pintype "passive"))
    )
    (net (code "5") (name "/A1") (class "Default")
      (node (ref "X4") (pin "A18") (pinfunction "A18_A18") (pintype "passive"))
    )
    (net (code "6") (name "/A2") (class "Default")
      (node (ref "X4") (pin "B17") (pinfunction "B17_B17") (pintype "passive"))
    )
    (net (code "7") (name "/A3") (class "Default")
      (node (ref "X4") (pin "A17") (pinfunction "A17_A17") (pintype "passive"))
    )
    (net (code "8") (name "/ABUS0") (class "Default")
      (node (ref "X3") (pin "ABUS0") (pinfunction "ABUS0_ABUS0") (pintype "passive"))
      (node (ref "X4") (pin "A5") (pinfunction "A5_A5") (pintype "passive"))
    )
    (net (code "9") (name "/ABUS1") (class "Default")
      (node (ref "X3") (pin "ABUS1") (pinfunction "ABUS1_ABUS1") (pintype "passive"))
      (node (ref "X4") (pin "B5") (pinfunction "B5_B5") (pintype "passive"))
    )
    (net (code "10") (name "/ABUS2") (class "Default")
      (node (ref "X3") (pin "ABUS2") (pinfunction "ABUS2_ABUS2") (pintype "passive"))
      (node (ref "X4") (pin "A4") (pinfunction "A4_A4") (pintype "passive"))
    )
    (net (code "11") (name "/ABUS3") (class "Default")
      (node (ref "X3") (pin "ABUS3") (pinfunction "ABUS3_ABUS3") (pintype "passive"))
      (node (ref "X4") (pin "B4") (pinfunction "B4_B4") (pintype "passive"))
    )
    (net (code "12") (name "/ABUS4") (class "Default")
      (node (ref "X3") (pin "ABUS4") (pinfunction "ABUS4_ABUS4") (pintype "passive"))
      (node (ref "X4") (pin "A3") (pinfunction "A3_A3") (pintype "passive"))
    )
    (net (code "13") (name "/ABUS5") (class "Default")
      (node (ref "X3") (pin "ABUS5") (pinfunction "ABUS5_ABUS5") (pintype "passive"))
      (node (ref "X4") (pin "B3") (pinfunction "B3_B3") (pintype "passive"))
    )
    (net (code "14") (name "/ABUS6") (class "Default")
      (node (ref "X3") (pin "ABUS6") (pinfunction "ABUS6_ABUS6") (pintype "passive"))
      (node (ref "X4") (pin "A2") (pinfunction "A2_A2") (pintype "passive"))
    )
    (net (code "15") (name "/ABUS7") (class "Default")
      (node (ref "X3") (pin "ABUS7") (pinfunction "ABUS7_ABUS7") (pintype "passive"))
      (node (ref "X4") (pin "B2") (pinfunction "B2_B2") (pintype "passive"))
    )
    (net (code "17") (name "/ALERT#") (class "Default")
      (node (ref "J11") (pin "5") (pinfunction "5_5") (pintype "passive"))
    )
    (net (code "18") (name "/CLK") (class "Default")
      (node (ref "J11") (pin "7") (pinfunction "7_7") (pintype "passive"))
    )
    (net (code "19") (name "/CS") (class "Default")
      (node (ref "R121") (pin "1") (pinfunction "1_1") (pintype "passive"))
      (node (ref "X4") (pin "B15") (pinfunction "B15_B15") (pintype "passive"))
    )
    (net (code "20") (name "/DATA") (class "Default")
      (node (ref "J11") (pin "9") (pinfunction "9_9") (pintype "passive"))
    )
    (net (code "21") (name "/DRV1") (class "Default")
      (node (ref "Q1") (pin "1") (pinfunction "G_1") (pintype "passive"))
      (node (ref "R1") (pin "2") (pinfunction "2_2") (pintype "passive"))
    )
    (net (code "22") (name "/DRV2") (class "Default")
      (node (ref "Q2") (pin "1") (pinfunction "G_1") (pintype "passive"))
      (node (ref "R2") (pin "2") (pinfunction "2_2") (pintype "passive"))
    )
    (net (code "23") (name "/DRV3") (class "Default")
      (node (ref "Q3") (pin "1") (pinfunction "G_1") (pintype "passive"))
      (node (ref "R3") (pin "2") (pinfunction "2_2") (pintype "passive"))
    )
    (net (code "24") (name "/DRV4") (class "Default")
      (node (ref "Q4") (pin "1") (pinfunction "G_1") (pintype "passive"))
      (node (ref "R4") (pin "2") (pinfunction "2_2") (pintype "passive"))
    )
    (net (code "25") (name "/DRV5") (class "Default")
      (node (ref "Q5") (pin "1") (pinfunction "G_1") (pintype "passive"))
      (node (ref "R5") (pin "2") (pinfunction "2_2") (pintype "passive"))
    )
    (net (code "26") (name "/DRV6") (class "Default")
      (node (ref "Q6") (pin "1") (pinfunction "G_1") (pintype "passive"))
      (node (ref "R6") (pin "2") (pinfunction "2_2") (pintype "passive"))
    )
    (net (code "27") (name "/DRV7") (class "Default")
      (node (ref "Q7") (pin "1") (pinfunction "G_1") (pintype "passive"))
      (node (ref "R7") (pin "2") (pinfunction "2_2") (pintype "passive"))
    )
    (net (code "28") (name "/DRV8") (class "Default")
      (node (ref "Q8") (pin "1") (pinfunction "G_1") (pintype "passive"))
      (node (ref "R8") (pin "2") (pinfunction "2_2") (pintype "passive"))
    )
    (net (code "29") (name "/DRV9") (class "Default")
      (node (ref "Q9") (pin "1") (pinfunction "G_1") (pintype "passive"))
      (node (ref "R9") (pin "2") (pinfunction "2_2") (pintype "passive"))
    )
    (net (code "30") (name "/DRV10") (class "Default")
      (node (ref "Q10") (pin "1") (pinfunction "G_1") (pintype "passive"))
      (node (ref "R10") (pin "2") (pinfunction "2_2") (pintype "passive"))
    )
    (net (code "31") (name "/DRV11") (class "Default")
      (node (ref "Q11") (pin "1") (pinfunction "G_1") (pintype "passive"))
      (node (ref "R11") (pin "2") (pinfunction "2_2") (pintype "passive"))
    )
    (net (code "32") (name "/DRV12") (class "Default")
      (node (ref "Q12") (pin "1") (pinfunction "G_1") (pintype "passive"))
      (node (ref "R12") (pin "2") (pinfunction "2_2") (pintype "passive"))
    )
    (net (code "33") (name "/DRV13") (class "Default")
      (node (ref "Q13") (pin "1") (pinfunction "G_1") (pintype "passive"))
      (node (ref "R13") (pin "2") (pinfunction "2_2") (pintype "passive"))
    )
    (net (code "34") (name "/DRV14") (class "Default")
      (node (ref "Q14") (pin "1") (pinfunction "G_1") (pintype "passive"))
      (node (ref "R14") (pin "2") (pinfunction "2_2") (pintype "passive"))
    )
    (net (code "35") (name "/DRV15") (class "Default")
      (node (ref "Q15") (pin "1") (pinfunction "G_1") (pintype "passive"))
      (node (ref "R15") (pin "2") (pinfunction "2_2") (pintype "passive"))
    )
    (net (code "36") (name "/DRV16") (class "Default")
      (node (ref "Q16") (pin "1") (pinfunction "G_1") (pintype "passive"))
      (node (ref "R16") (pin "2") (pinfunction "2_2") (pintype "passive"))
    )
    (net (code "37") (name "/DRV17") (class "Default")
      (node (ref "Q17") (pin "1") (pinfunction "G_1") (pintype "passive"))
      (node (ref "R17") (pin "2") (pinfunction "2_2") (pintype "passive"))
    )
    (net (code "38") (name "/DRV18") (class "Default")
      (node (ref "Q18") (pin "1") (pinfunction "G_1") (pintype "passive"))
      (node (ref "R18") (pin "2") (pinfunction "2_2") (pintype "passive"))
    )
    (net (code "39") (name "/DRV19") (class "Default")
      (node (ref "Q19") (pin "1") (pinfunction "G_1") (pintype "passive"))
      (node (ref "R19") (pin "2") (pinfunction "2_2") (pintype "passive"))
    )
    (net (code "40") (name "/DRV20") (class "Default")
      (node (ref "Q20") (pin "1") (pinfunction "G_1") (pintype "passive"))
      (node (ref "R20") (pin "2") (pinfunction "2_2") (pintype "passive"))
    )
    (net (code "41") (name "/DRV21") (class "Default")
      (node (ref "Q21") (pin "1") (pinfunction "G_1") (pintype "passive"))
      (node (ref "R21") (pin "2") (pinfunction "2_2") (pintype "passive"))
    )
    (net (code "42") (name "/DRV22") (class "Default")
      (node (ref "Q22") (pin "1") (pinfunction "G_1") (pintype "passive"))
      (node (ref "R22") (pin "2") (pinfunction "2_2") (pintype "passive"))
    )
    (net (code "43") (name "/DRV23") (class "Default")
      (node (ref "Q23") (pin "1") (pinfunction "G_1") (pintype "passive"))
      (node (ref "R23") (pin "2") (pinfunction "2_2") (pintype "passive"))
    )
    (net (code "44") (name "/DRV24") (class "Default")
      (node (ref "Q24") (pin "1") (pinfunction "G_1") (pintype "passive"))
      (node (ref "R24") (pin "2") (pinfunction "2_2") (pintype "passive"))
    )
    (net (code "45") (name "/DRV25") (class "Default")
      (node (ref "Q25") (pin "1") (pinfunction "G_1") (pintype "passive"))
      (node (ref "R25") (pin "2") (pinfunction "2_2") (pintype "passive"))
    )
    (net (code "46") (name "/DRV26") (class "Default")
      (node (ref "Q26") (pin "1") (pinfunction "G_1") (pintype "passive"))
      (node (ref "R26") (pin "2") (pinfunction "2_2") (pintype "passive"))
    )
    (net (code "47") (name "/DRV27") (class "Default")
      (node (ref "Q27") (pin "1") (pinfunction "G_1") (pintype "passive"))
      (node (ref "R27") (pin "2") (pinfunction "2_2") (pintype "passive"))
    )
    (net (code "48") (name "/DRV28") (class "Default")
      (node (ref "Q28") (pin "1") (pinfunction "G_1") (pintype "passive"))
      (node (ref "R28") (pin "2") (pinfunction "2_2") (pintype "passive"))
    )
    (net (code "49") (name "/DRV29") (class "Default")
      (node (ref "Q29") (pin "1") (pinfunction "G_1") (pintype "passive"))
      (node (ref "R29") (pin "2") (pinfunction "2_2") (pintype "passive"))
    )
    (net (code "50") (name "/DRV30") (class "Default")
      (node (ref "Q30") (pin "1") (pinfunction "G_1") (pintype "passive"))
      (node (ref "R30") (pin "2") (pinfunction "2_2") (pintype "passive"))
    )
    (net (code "51") (name "/DRV31") (class "Default")
      (node (ref "Q31") (pin "1") (pinfunction "G_1") (pintype "passive"))
      (node (ref "R31") (pin "2") (pinfunction "2_2") (pintype "passive"))
    )
    (net (code "52") (name "/DRV32") (class "Default")
      (node (ref "Q32") (pin "1") (pinfunction "G_1") (pintype "passive"))
      (node (ref "R32") (pin "2") (pinfunction "2_2") (pintype "passive"))
    )
    (net (code "53") (name "/DRV33") (class "Default")
      (node (ref "Q33") (pin "1") (pinfunction "G_1") (pintype "passive"))
      (node (ref "R33") (pin "2") (pinfunction "2_2") (pintype "passive"))
    )
    (net (code "54") (name "/DRV34") (class "Default")
      (node (ref "Q34") (pin "1") (pinfunction "G_1") (pintype "passive"))
      (node (ref "R34") (pin "2") (pinfunction "2_2") (pintype "passive"))
    )
    (net (code "55") (name "/DRV35") (class "Default")
      (node (ref "Q35") (pin "1") (pinfunction "G_1") (pintype "passive"))
      (node (ref "R35") (pin "2") (pinfunction "2_2") (pintype "passive"))
    )
    (net (code "56") (name "/DRV36") (class "Default")
      (node (ref "Q36") (pin "1") (pinfunction "G_1") (pintype "passive"))
      (node (ref "R36") (pin "2") (pinfunction "2_2") (pintype "passive"))
    )
    (net (code "57") (name "/DRV37") (class "Default")
      (node (ref "Q37") (pin "1") (pinfunction "G_1") (pintype "passive"))
      (node (ref "R37") (pin "2") (pinfunction "2_2") (pintype "passive"))
    )
    (net (code "58") (name "/DRV38") (class "Default")
      (node (ref "Q38") (pin "1") (pinfunction "G_1") (pintype "passive"))
      (node (ref "R38") (pin "2") (pinfunction "2_2") (pintype "passive"))
    )
    (net (code "59") (name "/DRV39") (class "Default")
      (node (ref "Q39") (pin "1") (pinfunction "G_1") (pintype "passive"))
      (node (ref "R39") (pin "2") (pinfunction "2_2") (pintype "passive"))
    )
    (net (code "60") (name "/DRV40") (class "Default")
      (node (ref "Q40") (pin "1") (pinfunction "G_1") (pintype "passive"))
      (node (ref "R40") (pin "2") (pinfunction "2_2") (pintype "passive"))
    )
    (net (code "61") (name "/DRV41") (class "Default")
      (node (ref "Q41") (pin "1") (pinfunction "G_1") (pintype "passive"))
      (node (ref "R41") (pin "2") (pinfunction "2_2") (pintype "passive"))
    )
    (net (code "62") (name "/DRV42") (class "Default")
      (node (ref "Q42") (pin "1") (pinfunction "G_1") (pintype "passive"))
      (node (ref "R42") (pin "2") (pinfunction "2_2") (pintype "passive"))
    )
    (net (code "63") (name "/DRV43") (class "Default")
      (node (ref "Q43") (pin "1") (pinfunction "G_1") (pintype "passive"))
      (node (ref "R48") (pin "2") (pinfunction "2_2") (pintype "passive"))
    )
    (net (code "64") (name "/DRV44") (class "Default")
      (node (ref "Q44") (pin "1") (pinfunction "G_1") (pintype "passive"))
      (node (ref "R49") (pin "2") (pinfunction "2_2") (pintype "passive"))
    )
    (net (code "65") (name "/DRV45") (class "Default")
      (node (ref "Q45") (pin "1") (pinfunction "G_1") (pintype "passive"))
      (node (ref "R50") (pin "2") (pinfunction "2_2") (pintype "passive"))
    )
    (net (code "66") (name "/DRV46") (class "Default")
      (node (ref "Q46") (pin "1") (pinfunction "G_1") (pintype "passive"))
      (node (ref "R51") (pin "2") (pinfunction "2_2") (pintype "passive"))
    )
    (net (code "67") (name "/DRV47") (class "Default")
      (node (ref "Q47") (pin "1") (pinfunction "G_1") (pintype "passive"))
      (node (ref "R52") (pin "2") (pinfunction "2_2") (pintype "passive"))
    )
    (net (code "68") (name "/DRV48") (class "Default")
      (node (ref "Q48") (pin "1") (pinfunction "G_1") (pintype "passive"))
      (node (ref "R53") (pin "2") (pinfunction "2_2") (pintype "passive"))
    )
    (net (code "69") (name "/DRV49") (class "Default")
      (node (ref "Q49") (pin "1") (pinfunction "G_1") (pintype "passive"))
      (node (ref "R54") (pin "2") (pinfunction "2_2") (pintype "passive"))
    )
    (net (code "70") (name "/DRV50") (class "Default")
      (node (ref "Q50") (pin "1") (pinfunction "G_1") (pintype "passive"))
      (node (ref "R55") (pin "2") (pinfunction "2_2") (pintype "passive"))
    )
    (net (code "71") (name "/DRV51") (class "Default")
      (node (ref "Q51") (pin "1") (pinfunction "G_1") (pintype "passive"))
      (node (ref "R56") (pin "2") (pinfunction "2_2") (pintype "passive"))
    )
    (net (code "72") (name "/DRV52") (class "Default")
      (node (ref "Q52") (pin "1") (pinfunction "G_1") (pintype "passive"))
      (node (ref "R57") (pin "2") (pinfunction "2_2") (pintype "passive"))
    )
    (net (code "73") (name "/DRV53") (class "Default")
      (node (ref "Q53") (pin "1") (pinfunction "G_1") (pintype "passive"))
      (node (ref "R58") (pin "2") (pinfunction "2_2") (pintype "passive"))
    )
    (net (code "74") (name "/DRV54") (class "Default")
      (node (ref "Q54") (pin "1") (pinfunction "G_1") (pintype "passive"))
      (node (ref "R59") (pin "2") (pinfunction "2_2") (pintype "passive"))
    )
    (net (code "75") (name "/DRV55") (class "Default")
      (node (ref "Q55") (pin "1") (pinfunction "G_1") (pintype "passive"))
      (node (ref "R60") (pin "2") (pinfunction "2_2") (pintype "passive"))
    )
    (net (code "76") (name "/DRV56") (class "Default")
      (node (ref "Q56") (pin "1") (pinfunction "G_1") (pintype "passive"))
      (node (ref "R61") (pin "2") (pinfunction "2_2") (pintype "passive"))
    )
    (net (code "77") (name "/DRV57") (class "Default")
      (node (ref "Q57") (pin "1") (pinfunction "G_1") (pintype "passive"))
      (node (ref "R62") (pin "2") (pinfunction "2_2") (pintype "passive"))
    )
    (net (code "78") (name "/DRV58") (class "Default")
      (node (ref "Q58") (pin "1") (pinfunction "G_1") (pintype "passive"))
      (node (ref "R63") (pin "2") (pinfunction "2_2") (pintype "passive"))
    )
    (net (code "79") (name "/DRV59") (class "Default")
      (node (ref "Q59") (pin "1") (pinfunction "G_1") (pintype "passive"))
      (node (ref "R64") (pin "2") (pinfunction "2_2") (pintype "passive"))
    )
    (net (code "80") (name "/DRV60") (class "Default")
      (node (ref "Q60") (pin "1") (pinfunction "G_1") (pintype "passive"))
      (node (ref "R65") (pin "2") (pinfunction "2_2") (pintype "passive"))
    )
    (net (code "81") (name "/DRV61") (class "Default")
      (node (ref "Q61") (pin "1") (pinfunction "G_1") (pintype "passive"))
      (node (ref "R66") (pin "2") (pinfunction "2_2") (pintype "passive"))
    )
    (net (code "82") (name "/DRV62") (class "Default")
      (node (ref "Q62") (pin "1") (pinfunction "G_1") (pintype "passive"))
      (node (ref "R67") (pin "2") (pinfunction "2_2") (pintype "passive"))
    )
    (net (code "83") (name "/DRV63") (class "Default")
      (node (ref "Q63") (pin "1") (pinfunction "G_1") (pintype "passive"))
      (node (ref "R68") (pin "2") (pinfunction "2_2") (pintype "passive"))
    )
    (net (code "84") (name "/DRV64") (class "Default")
      (node (ref "Q64") (pin "1") (pinfunction "G_1") (pintype "passive"))
      (node (ref "R69") (pin "2") (pinfunction "2_2") (pintype "passive"))
    )
    (net (code "86") (name "/MISO") (class "Default")
      (node (ref "X4") (pin "A15") (pinfunction "A15_A15") (pintype "passive"))
    )
    (net (code "87") (name "/MOSI") (class "Default")
      (node (ref "X4") (pin "A14") (pinfunction "A14_A14") (pintype "passive"))
    )
    (net (code "88") (name "/SCLK") (class "Default")
      (node (ref "X4") (pin "B14") (pinfunction "B14_B14") (pintype "passive"))
    )
    (net (code "96") (name "3V3IO") (class "Default")
      (node (ref "J12") (pin "1") (pinfunction "1_1") (pintype "passive"))
      (node (ref "R121") (pin "2") (pinfunction "2_2") (pintype "passive"))
    )
    (net (code "97") (name "5V0R") (class "Default")
      (node (ref "D12") (pin "1") (pinfunction "Anode_1") (pintype "passive"))
      (node (ref "K1") (pin "1") (pinfunction "+_1") (pintype "passive"))
      (node (ref "K10") (pin "1") (pinfunction "+_1") (pintype "passive"))
      (node (ref "K11") (pin "1") (pinfunction "+_1") (pintype "passive"))
      (node (ref "K12") (pin "1") (pinfunction "+_1") (pintype "passive"))
      (node (ref "K13") (pin "1") (pinfunction "+_1") (pintype "passive"))
      (node (ref "K14") (pin "1") (pinfunction "+_1") (pintype "passive"))
      (node (ref "K15") (pin "1") (pinfunction "+_1") (pintype "passive"))
      (node (ref "K16") (pin "1") (pinfunction "+_1") (pintype "passive"))
      (node (ref "K17") (pin "1") (pinfunction "+_1") (pintype "passive"))
      (node (ref "K18") (pin "1") (pinfunction "+_1") (pintype "passive"))
      (node (ref "K19") (pin "1") (pinfunction "+_1") (pintype "passive"))
      (node (ref "K2") (pin "1") (pinfunction "+_1") (pintype "passive"))
      (node (ref "K20") (pin "1") (pinfunction "+_1") (pintype "passive"))
      (node (ref "K21") (pin "1") (pinfunction "+_1") (pintype "passive"))
      (node (ref "K22") (pin "1") (pinfunction "+_1") (pintype "passive"))
      (node (ref "K23") (pin "1") (pinfunction "+_1") (pintype "passive"))
      (node (ref "K24") (pin "1") (pinfunction "+_1") (pintype "passive"))
      (node (ref "K25") (pin "1") (pinfunction "+_1") (pintype "passive"))
      (node (ref "K26") (pin "1") (pinfunction "+_1") (pintype "passive"))
      (node (ref "K27") (pin "1") (pinfunction "+_1") (pintype "passive"))
      (node (ref "K28") (pin "1") (pinfunction "+_1") (pintype "passive"))
      (node (ref "K29") (pin "1") (pinfunction "+_1") (pintype "passive"))
      (node (ref "K3") (pin "1") (pinfunction "+_1") (pintype "passive"))
      (node (ref "K30") (pin "1") (pinfunction "+_1") (pintype "passive"))
      (node (ref "K31") (pin "1") (pinfunction "+_1") (pintype "passive"))
      (node (ref "K32") (pin "1") (pinfunction "+_1") (pintype "passive"))
      (node (ref "K33") (pin "1") (pinfunction "+_1") (pintype "passive"))
      (node (ref "K34") (pin "1") (pinfunction "+_1") (pintype "passive"))
      (node (ref "K35") (pin "1") (pinfunction "+_1") (pintype "passive"))
      (node (ref "K36") (pin "1") (pinfunction "+_1") (pintype "passive"))
      (node (ref "K37") (pin "1") (pinfunction "+_1") (pintype "passive"))
      (node (ref "K38") (pin "1") (pinfunction "+_1") (pintype "passive"))
      (node (ref "K39") (pin "1") (pinfunction "+_1") (pintype "passive"))
      (node (ref "K4") (pin "1") (pinfunction "+_1") (pintype "passive"))
      (node (ref "K40") (pin "1") (pinfunction "+_1") (pintype "passive"))
      (node (ref "K41") (pin "1") (pinfunction "+_1") (pintype "passive"))
      (node (ref "K42") (pin "1") (pinfunction "+_1") (pintype "passive"))
      (node (ref "K43") (pin "1") (pinfunction "+_1") (pintype "passive"))
      (node (ref "K44") (pin "1") (pinfunction "+_1") (pintype "passive"))
      (node (ref "K45") (pin "1") (pinfunction "+_1") (pintype "passive"))
      (node (ref "K46") (pin "1") (pinfunction "+_1") (pintype "passive"))
      (node (ref "K47") (pin "1") (pinfunction "+_1") (pintype "passive"))
      (node (ref "K48") (pin "1") (pinfunction "+_1") (pintype "passive"))
      (node (ref "K49") (pin "1") (pinfunction "+_1") (pintype "passive"))
      (node (ref "K5") (pin "1") (pinfunction "+_1") (pintype "passive"))
      (node (ref "K50") (pin "1") (pinfunction "+_1") (pintype "passive"))
      (node (ref "K51") (pin "1") (pinfunction "+_1") (pintype "passive"))
      (node (ref "K52") (pin "1") (pinfunction "+_1") (pintype "passive"))
      (node (ref "K53") (pin "1") (pinfunction "+_1") (pintype "passive"))
      (node (ref "K54") (pin "1") (pinfunction "+_1") (pintype "passive"))
      (node (ref "K55") (pin "1") (pinfunction "+_1") (pintype "passive"))
      (node (ref "K56") (pin "1") (pinfunction "+_1") (pintype "passive"))
      (node (ref "K57") (pin "1") (pinfunction "+_1") (pintype "passive"))
      (node (ref "K58") (pin "1") (pinfunction "+_1") (pintype "passive"))
      (node (ref "K59") (pin "1") (pinfunction "+_1") (pintype "passive"))
      (node (ref "K6") (pin "1") (pinfunction "+_1") (pintype "passive"))
      (node (ref "K60") (pin "1") (pinfunction "+_1") (pintype "passive"))
      (node (ref "K61") (pin "1") (pinfunction "+_1") (pintype "passive"))
      (node (ref "K62") (pin "1") (pinfunction "+_1") (pintype "passive"))
      (node (ref "K63") (pin "1") (pinfunction "+_1") (pintype "passive"))
      (node (ref "K64") (pin "1") (pinfunction "+_1") (pintype "passive"))
      (node (ref "K7") (pin "1") (pinfunction "+_1") (pintype "passive"))
      (node (ref "K8") (pin "1") (pinfunction "+_1") (pintype "passive"))
      (node (ref "K9") (pin "1") (pinfunction "+_1") (pintype "passive"))
      (node (ref "TP5") (pin "1") (pinfunction "1_1") (pintype "passive"))
      (node (ref "X4") (pin "A10") (pinfunction "A10_A10") (pintype "passive"))
      (node (ref "X4") (pin "A7") (pinfunction "A7_A7") (pintype "passive"))
      (node (ref "X4") (pin "A8") (pinfunction "A8_A8") (pintype "passive"))
      (node (ref "X4") (pin "A9") (pinfunction "A9_A9") (pintype "passive"))
      (node (ref "X4") (pin "B10") (pinfunction "B10_B10") (pintype "passive"))
      (node (ref "X4") (pin "B7") (pinfunction "B7_B7") (pintype "passive"))
      (node (ref "X4") (pin "B8") (pinfunction "B8_B8") (pintype "passive"))
      (node (ref "X4") (pin "B9") (pinfunction "B9_B9") (pintype "passive"))
    )
    (net (code "98") (name "12V0") (class "Default")
      (node (ref "J11") (pin "1") (pinfunction "1_1") (pintype "passive"))
      (node (ref "TP6") (pin "1") (pinfunction "1_1") (pintype "passive"))
      (node (ref "X4") (pin "A11") (pinfunction "A11_A11") (pintype "passive"))
      (node (ref "X4") (pin "A12") (pinfunction "A12_A12") (pintype "passive"))
      (node (ref "X4") (pin "B11") (pinfunction "B11_B11") (pintype "passive"))
      (node (ref "X4") (pin "B12") (pinfunction "B12_B12") (pintype "passive"))
    )
    (net (code "99") (name "GND") (class "Default")
      (node (ref "J11") (pin "10") (pinfunction "10_10") (pintype "passive"))
      (node (ref "J11") (pin "2") (pinfunction "2_2") (pintype "passive"))
      (node (ref "J11") (pin "4") (pinfunction "4_4") (pintype "passive"))
      (node (ref "J11") (pin "6") (pinfunction "6_6") (pintype "passive"))
      (node (ref "J11") (pin "8") (pinfunction "8_8") (pintype "passive"))
      (node (ref "Q1") (pin "2") (pinfunction "S_2") (pintype "passive"))
      (node (ref "Q10") (pin "2") (pinfunction "S_2") (pintype "passive"))
      (node (ref "Q11") (pin "2") (pinfunction "S_2") (pintype "passive"))
      (node (ref "Q12") (pin "2") (pinfunction "S_2") (pintype "passive"))
      (node (ref "Q13") (pin "2") (pinfunction "S_2") (pintype "passive"))
      (node (ref "Q14") (pin "2") (pinfunction "S_2") (pintype "passive"))
      (node (ref "Q15") (pin "2") (pinfunction "S_2") (pintype "passive"))
      (node (ref "Q16") (pin "2") (pinfunction "S_2") (pintype "passive"))
      (node (ref "Q17") (pin "2") (pinfunction "S_2") (pintype "passive"))
      (node (ref "Q18") (pin "2") (pinfunction "S_2") (pintype "passive"))
      (node (ref "Q19") (pin "2") (pinfunction "S_2") (pintype "passive"))
      (node (ref "Q2") (pin "2") (pinfunction "S_2") (pintype "passive"))
      (node (ref "Q20") (pin "2") (pinfunction "S_2") (pintype "passive"))
      (node (ref "Q21") (pin "2") (pinfunction "S_2") (pintype "passive"))
      (node (ref "Q22") (pin "2") (pinfunction "S_2") (pintype "passive"))
      (node (ref "Q23") (pin "2") (pinfunction "S_2") (pintype "passive"))
      (node (ref "Q24") (pin "2") (pinfunction "S_2") (pintype "passive"))
      (node (ref "Q25") (pin "2") (pinfunction "S_2") (pintype "passive"))
      (node (ref "Q26") (pin "2") (pinfunction "S_2") (pintype "passive"))
      (node (ref "Q27") (pin "2") (pinfunction "S_2") (pintype "passive"))
      (node (ref "Q28") (pin "2") (pinfunction "S_2") (pintype "passive"))
      (node (ref "Q29") (pin "2") (pinfunction "S_2") (pintype "passive"))
      (node (ref "Q3") (pin "2") (pinfunction "S_2") (pintype "passive"))
      (node (ref "Q30") (pin "2") (pinfunction "S_2") (pintype "passive"))
      (node (ref "Q31") (pin "2") (pinfunction "S_2") (pintype "passive"))
      (node (ref "Q32") (pin "2") (pinfunction "S_2") (pintype "passive"))
      (node (ref "Q33") (pin "2") (pinfunction "S_2") (pintype "passive"))
      (node (ref "Q34") (pin "2") (pinfunction "S_2") (pintype "passive"))
      (node (ref "Q35") (pin "2") (pinfunction "S_2") (pintype "passive"))
      (node (ref "Q36") (pin "2") (pinfunction "S_2") (pintype "passive"))
      (node (ref "Q37") (pin "2") (pinfunction "S_2") (pintype "passive"))
      (node (ref "Q38") (pin "2") (pinfunction "S_2") (pintype "passive"))
      (node (ref "Q39") (pin "2") (pinfunction "S_2") (pintype "passive"))
      (node (ref "Q4") (pin "2") (pinfunction "S_2") (pintype "passive"))
      (node (ref "Q40") (pin "2") (pinfunction "S_2") (pintype "passive"))
      (node (ref "Q41") (pin "2") (pinfunction "S_2") (pintype "passive"))
      (node (ref "Q42") (pin "2") (pinfunction "S_2") (pintype "passive"))
      (node (ref "Q43") (pin "2") (pinfunction "S_2") (pintype "passive"))
      (node (ref "Q44") (pin "2") (pinfunction "S_2") (pintype "passive"))
      (node (ref "Q45") (pin "2") (pinfunction "S_2") (pintype "passive"))
      (node (ref "Q46") (pin "2") (pinfunction "S_2") (pintype "passive"))
      (node (ref "Q47") (pin "2") (pinfunction "S_2") (pintype "passive"))
      (node (ref "Q48") (pin "2") (pinfunction "S_2") (pintype "passive"))
      (node (ref "Q49") (pin "2") (pinfunction "S_2") (pintype "passive"))
      (node (ref "Q5") (pin "2") (pinfunction "S_2") (pintype "passive"))
      (node (ref "Q50") (pin "2") (pinfunction "S_2") (pintype "passive"))
      (node (ref "Q51") (pin "2") (pinfunction "S_2") (pintype "passive"))
      (node (ref "Q52") (pin "2") (pinfunction "S_2") (pintype "passive"))
      (node (ref "Q53") (pin "2") (pinfunction "S_2") (pintype "passive"))
      (node (ref "Q54") (pin "2") (pinfunction "S_2") (pintype "passive"))
      (node (ref "Q55") (pin "2") (pinfunction "S_2") (pintype "passive"))
      (node (ref "Q56") (pin "2") (pinfunction "S_2") (pintype "passive"))
      (node (ref "Q57") (pin "2") (pinfunction "S_2") (pintype "passive"))
      (node (ref "Q58") (pin "2") (pinfunction "S_2") (pintype "passive"))
      (node (ref "Q59") (pin "2") (pinfunction "S_2") (pintype "passive"))
      (node (ref "Q6") (pin "2") (pinfunction "S_2") (pintype "passive"))
      (node (ref "Q60") (pin "2") (pinfunction "S_2") (pintype "passive"))
      (node (ref "Q61") (pin "2") (pinfunction "S_2") (pintype "passive"))
      (node (ref "Q62") (pin "2") (pinfunction "S_2") (pintype "passive"))
      (node (ref "Q63") (pin "2") (pinfunction "S_2") (pintype "passive"))
      (node (ref "Q64") (pin "2") (pinfunction "S_2") (pintype "passive"))
      (node (ref "Q7") (pin "2") (pinfunction "S_2") (pintype "passive"))
      (node (ref "Q8") (pin "2") (pinfunction "S_2") (pintype "passive"))
      (node (ref "Q9") (pin "2") (pinfunction "S_2") (pintype "passive"))
      (node (ref "R1") (pin "1") (pinfunction "1_1") (pintype "passive"))
      (node (ref "R10") (pin "1") (pinfunction "1_1") (pintype "passive"))
      (node (ref "R11") (pin "1") (pinfunction "1_1") (pintype "passive"))
      (node (ref "R12") (pin "1") (pinfunction "1_1") (pintype "passive"))
      (node (ref "R125") (pin "1") (pinfunction "1_1") (pintype "passive"))
      (node (ref "R13") (pin "1") (pinfunction "1_1") (pintype "passive"))
      (node (ref "R14") (pin "1") (pinfunction "1_1") (pintype "passive"))
      (node (ref "R15") (pin "1") (pinfunction "1_1") (pintype "passive"))
      (node (ref "R16") (pin "1") (pinfunction "1_1") (pintype "passive"))
      (node (ref "R17") (pin "1") (pinfunction "1_1") (pintype "passive"))
      (node (ref "R18") (pin "1") (pinfunction "1_1") (pintype "passive"))
      (node (ref "R19") (pin "1") (pinfunction "1_1") (pintype "passive"))
      (node (ref "R2") (pin "1") (pinfunction "1_1") (pintype "passive"))
      (node (ref "R20") (pin "1") (pinfunction "1_1") (pintype "passive"))
      (node (ref "R21") (pin "1") (pinfunction "1_1") (pintype "passive"))
      (node (ref "R22") (pin "1") (pinfunction "1_1") (pintype "passive"))
      (node (ref "R23") (pin "1") (pinfunction "1_1") (pintype "passive"))
      (node (ref "R24") (pin "1") (pinfunction "1_1") (pintype "passive"))
      (node (ref "R25") (pin "1") (pinfunction "1_1") (pintype "passive"))
      (node (ref "R26") (pin "1") (pinfunction "1_1") (pintype "passive"))
      (node (ref "R27") (pin "1") (pinfunction "1_1") (pintype "passive"))
      (node (ref "R28") (pin "1") (pinfunction "1_1") (pintype "passive"))
      (node (ref "R29") (pin "1") (pinfunction "1_1") (pintype "passive"))
      (node (ref "R3") (pin "1") (pinfunction "1_1") (pintype "passive"))
      (node (ref "R30") (pin "1") (pinfunction "1_1") (pintype "passive"))
      (node (ref "R31") (pin "1") (pinfunction "1_1") (pintype "passive"))
      (node (ref "R32") (pin "1") (pinfunction "1_1") (pintype "passive"))
      (node (ref "R33") (pin "1") (pinfunction "1_1") (pintype "passive"))
      (node (ref "R34") (pin "1") (pinfunction "1_1") (pintype "passive"))
      (node (ref "R35") (pin "1") (pinfunction "1_1") (pintype "passive"))
      (node (ref "R36") (pin "1") (pinfunction "1_1") (pintype "passive"))
      (node (ref "R37") (pin "1") (pinfunction "1_1") (pintype "passive"))
      (node (ref "R38") (pin "1") (pinfunction "1_1") (pintype "passive"))
      (node (ref "R39") (pin "1") (pinfunction "1_1") (pintype "passive"))
      (node (ref "R4") (pin "1") (pinfunction "1_1") (pintype "passive"))
      (node (ref "R40") (pin "1") (pinfunction "1_1") (pintype "passive"))
      (node (ref "R41") (pin "1") (pinfunction "1_1") (pintype "passive"))
      (node (ref "R42") (pin "1") (pinfunction "1_1") (pintype "passive"))
      (node (ref "R48") (pin "1") (pinfunction "1_1") (pintype "passive"))
      (node (ref "R49") (pin "1") (pinfunction "1_1") (pintype "passive"))
      (node (ref "R5") (pin "1") (pinfunction "1_1") (pintype "passive"))
      (node (ref "R50") (pin "1") (pinfunction "1_1") (pintype "passive"))
      (node (ref "R51") (pin "1") (pinfunction "1_1") (pintype "passive"))
      (node (ref "R52") (pin "1") (pinfunction "1_1") (pintype "passive"))
      (node (ref "R53") (pin "1") (pinfunction "1_1") (pintype "passive"))
      (node (ref "R54") (pin "1") (pinfunction "1_1") (pintype "passive"))
      (node (ref "R55") (pin "1") (pinfunction "1_1") (pintype "passive"))
      (node (ref "R56") (pin "1") (pinfunction "1_1") (pintype "passive"))
      (node (ref "R57") (pin "1") (pinfunction "1_1") (pintype "passive"))
      (node (ref "R58") (pin "1") (pinfunction "1_1") (pintype "passive"))
      (node (ref "R59") (pin "1") (pinfunction "1_1") (pintype "passive"))
      (node (ref "R6") (pin "1") (pinfunction "1_1") (pintype "passive"))
      (node (ref "R60") (pin "1") (pinfunction "1_1") (pintype "passive"))
      (node (ref "R61") (pin "1") (pinfunction "1_1") (pintype "passive"))
      (node (ref "R62") (pin "1") (pinfunction "1_1") (pintype "passive"))
      (node (ref "R63") (pin "1") (pinfunction "1_1") (pintype "passive"))
      (node (ref "R64") (pin "1") (pinfunction "1_1") (pintype "passive"))
      (node (ref "R65") (pin "1") (pinfunction "1_1") (pintype "passive"))
      (node (ref "R66") (pin "1") (pinfunction "1_1") (pintype "passive"))
      (node (ref "R67") (pin "1") (pinfunction "1_1") (pintype "passive"))
      (node (ref "R68") (pin "1") (pinfunction "1_1") (pintype "passive"))
      (node (ref "R69") (pin "1") (pinfunction "1_1") (pintype "passive"))
      (node (ref "R7") (pin "1") (pinfunction "1_1") (pintype "passive"))
      (node (ref "R8") (pin "1") (pinfunction "1_1") (pintype "passive"))
      (node (ref "R9") (pin "1") (pinfunction "1_1") (pintype "passive"))
      (node (ref "TP5") (pin "2") (pinfunction "2_2") (pintype "passive"))
      (node (ref "TP6") (pin "2") (pinfunction "2_2") (pintype "passive"))
      (node (ref "X4") (pin "A1") (pinfunction "A1_A1") (pintype "passive"))
      (node (ref "X4") (pin "A13") (pinfunction "A13_A13") (pintype "passive"))
      (node (ref "X4") (pin "A16") (pinfunction "A16_A16") (pintype "passive"))
      (node (ref "X4") (pin "A6") (pinfunction "A6_A6") (pintype "passive"))
      (node (ref "X4") (pin "B1") (pinfunction "B1_B1") (pintype "passive"))
      (node (ref "X4") (pin "B13") (pinfunction "B13_B13") (pintype "passive"))
      (node (ref "X4") (pin "B16") (pinfunction "B16_B16") (pintype "passive"))
      (node (ref "X4") (pin "B6") (pinfunction "B6_B6") (pintype "passive"))
    )
    (net (code "100") (name "Net-(D12-Cathode)") (class "Default")
      (node (ref "D12") (pin "2") (pinfunction "Cathode_2") (pintype "passive"))
      (node (ref "R125") (pin "2") (pinfunction "2_2") (pintype "passive"))
    )
    (net (code "101") (name "Net-(J11-Pad3)") (class "Default")
      (node (ref "J11") (pin "3") (pinfunction "3_3") (pintype "passive"))
      (node (ref "J12") (pin "2") (pinfunction "2_2") (pintype "passive"))
    )
    (net (code "102") (name "Net-(K1A-CA)") (class "Default")
      (node (ref "K1") (pin "3") (pinfunction "CA_3") (pintype "passive"))
      (node (ref "X3") (pin "1") (pinfunction "1_1") (pintype "passive"))
    )
    (net (code "103") (name "Net-(K1A-CB)") (class "Default")
      (node (ref "K1") (pin "4") (pinfunction "CB_4") (pintype "passive"))
      (node (ref "X2") (pin "1") (pinfunction "1_1") (pintype "passive"))
    )
    (net (code "104") (name "Net-(K1B--)") (class "Default")
      (node (ref "K1") (pin "2") (pinfunction "-_2") (pintype "passive"))
      (node (ref "Q1") (pin "3") (pinfunction "D_3") (pintype "passive"))
    )
    (net (code "105") (name "Net-(K2A-CA)") (class "Default")
      (node (ref "K2") (pin "3") (pinfunction "CA_3") (pintype "passive"))
      (node (ref "X3") (pin "2") (pinfunction "2_2") (pintype "passive"))
    )
    (net (code "106") (name "Net-(K2A-CB)") (class "Default")
      (node (ref "K2") (pin "4") (pinfunction "CB_4") (pintype "passive"))
      (node (ref "X2") (pin "2") (pinfunction "2_2") (pintype "passive"))
    )
    (net (code "107") (name "Net-(K2B--)") (class "Default")
      (node (ref "K2") (pin "2") (pinfunction "-_2") (pintype "passive"))
      (node (ref "Q2") (pin "3") (pinfunction "D_3") (pintype "passive"))
    )
    (net (code "108") (name "Net-(K3A-CA)") (class "Default")
      (node (ref "K3") (pin "3") (pinfunction "CA_3") (pintype "passive"))
      (node (ref "X3") (pin "3") (pinfunction "3_3") (pintype "passive"))
    )
    (net (code "109") (name "Net-(K3A-CB)") (class "Default")
      (node (ref "K3") (pin "4") (pinfunction "CB_4") (pintype "passive"))
      (node (ref "X2") (pin "3") (pinfunction "3_3") (pintype "passive"))
    )
    (net (code "110") (name "Net-(K3B--)") (class "Default")
      (node (ref "K3") (pin "2") (pinfunction "-_2") (pintype "passive"))
      (node (ref "Q3") (pin "3") (pinfunction "D_3") (pintype "passive"))
    )
    (net (code "111") (name "Net-(K4A-CA)") (class "Default")
      (node (ref "K4") (pin "3") (pinfunction "CA_3") (pintype "passive"))
      (node (ref "X3") (pin "4") (pinfunction "4_4") (pintype "passive"))
    )
    (net (code "112") (name "Net-(K4A-CB)") (class "Default")
      (node (ref "K4") (pin "4") (pinfunction "CB_4") (pintype "passive"))
      (node (ref "X2") (pin "4") (pinfunction "4_4") (pintype "passive"))
    )
    (net (code "113") (name "Net-(K4B--)") (class "Default")
      (node (ref "K4") (pin "2") (pinfunction "-_2") (pintype "passive"))
      (node (ref "Q4") (pin "3") (pinfunction "D_3") (pintype "passive"))
    )
    (net (code "114") (name "Net-(K5A-CA)") (class "Default")
      (node (ref "K5") (pin "3") (pinfunction "CA_3") (pintype "passive"))
      (node (ref "X3") (pin "5") (pinfunction "5_5") (pintype "passive"))
    )
    (net (code "115") (name "Net-(K5A-CB)") (class "Default")
      (node (ref "K5") (pin "4") (pinfunction "CB_4") (pintype "passive"))
      (node (ref "X2") (pin "5") (pinfunction "5_5") (pintype "passive"))
    )
    (net (code "116") (name "Net-(K5B--)") (class "Default")
      (node (ref "K5") (pin "2") (pinfunction "-_2") (pintype "passive"))
      (node (ref "Q5") (pin "3") (pinfunction "D_3") (pintype "passive"))
    )
    (net (code "117") (name "Net-(K6A-CA)") (class "Default")
      (node (ref "K6") (pin "3") (pinfunction "CA_3") (pintype "passive"))
      (node (ref "X3") (pin "6") (pinfunction "6_6") (pintype "passive"))
    )
    (net (code "118") (name "Net-(K6A-CB)") (class "Default")
      (node (ref "K6") (pin "4") (pinfunction "CB_4") (pintype "passive"))
      (node (ref "X2") (pin "6") (pinfunction "6_6") (pintype "passive"))
    )
    (net (code "119") (name "Net-(K6B--)") (class "Default")
      (node (ref "K6") (pin "2") (pinfunction "-_2") (pintype "passive"))
      (node (ref "Q6") (pin "3") (pinfunction "D_3") (pintype "passive"))
    )
    (net (code "120") (name "Net-(K7A-CA)") (class "Default")
      (node (ref "K7") (pin "3") (pinfunction "CA_3") (pintype "passive"))
      (node (ref "X3") (pin "7") (pinfunction "7_7") (pintype "passive"))
    )
    (net (code "121") (name "Net-(K7A-CB)") (class "Default")
      (node (ref "K7") (pin "4") (pinfunction "CB_4") (pintype "passive"))
      (node (ref "X2") (pin "7") (pinfunction "7_7") (pintype "passive"))
    )
    (net (code "122") (name "Net-(K7B--)") (class "Default")
      (node (ref "K7") (pin "2") (pinfunction "-_2") (pintype "passive"))
      (node (ref "Q7") (pin "3") (pinfunction "D_3") (pintype "passive"))
    )
    (net (code "123") (name "Net-(K8A-CA)") (class "Default")
      (node (ref "K8") (pin "3") (pinfunction "CA_3") (pintype "passive"))
      (node (ref "X3") (pin "8") (pinfunction "8_8") (pintype "passive"))
    )
    (net (code "124") (name "Net-(K8A-CB)") (class "Default")
      (node (ref "K8") (pin "4") (pinfunction "CB_4") (pintype "passive"))
      (node (ref "X2") (pin "8") (pinfunction "8_8") (pintype "passive"))
    )
    (net (code "125") (name "Net-(K8B--)") (class "Default")
      (node (ref "K8") (pin "2") (pinfunction "-_2") (pintype "passive"))
      (node (ref "Q8") (pin "3") (pinfunction "D_3") (pintype "passive"))
    )
    (net (code "126") (name "Net-(K9A-CA)") (class "Default")
      (node (ref "K9") (pin "3") (pinfunction "CA_3") (pintype "passive"))
      (node (ref "X3") (pin "9") (pinfunction "9_9") (pintype "passive"))
    )
    (net (code "127") (name "Net-(K9A-CB)") (class "Default")
      (node (ref "K9") (pin "4") (pinfunction "CB_4") (pintype "passive"))
      (node (ref "X2") (pin "9") (pinfunction "9_9") (pintype "passive"))
    )
    (net (code "128") (name "Net-(K9B--)") (class "Default")
      (node (ref "K9") (pin "2") (pinfunction "-_2") (pintype "passive"))
      (node (ref "Q9") (pin "3") (pinfunction "D_3") (pintype "passive"))
    )
    (net (code "129") (name "Net-(K10A-CA)") (class "Default")
      (node (ref "K10") (pin "3") (pinfunction "CA_3") (pintype "passive"))
      (node (ref "X3") (pin "10") (pinfunction "10_10") (pintype "passive"))
    )
    (net (code "130") (name "Net-(K10A-CB)") (class "Default")
      (node (ref "K10") (pin "4") (pinfunction "CB_4") (pintype "passive"))
      (node (ref "X2") (pin "10") (pinfunction "10_10") (pintype "passive"))
    )
    (net (code "131") (name "Net-(K10B--)") (class "Default")
      (node (ref "K10") (pin "2") (pinfunction "-_2") (pintype "passive"))
      (node (ref "Q10") (pin "3") (pinfunction "D_3") (pintype "passive"))
    )
    (net (code "132") (name "Net-(K11A-CA)") (class "Default")
      (node (ref "K11") (pin "3") (pinfunction "CA_3") (pintype "passive"))
      (node (ref "X3") (pin "11") (pinfunction "11_11") (pintype "passive"))
    )
    (net (code "133") (name "Net-(K11A-CB)") (class "Default")
      (node (ref "K11") (pin "4") (pinfunction "CB_4") (pintype "passive"))
      (node (ref "X2") (pin "11") (pinfunction "11_11") (pintype "passive"))
    )
    (net (code "134") (name "Net-(K11B--)") (class "Default")
      (node (ref "K11") (pin "2") (pinfunction "-_2") (pintype "passive"))
      (node (ref "Q11") (pin "3") (pinfunction "D_3") (pintype "passive"))
    )
    (net (code "135") (name "Net-(K12A-CA)") (class "Default")
      (node (ref "K12") (pin "3") (pinfunction "CA_3") (pintype "passive"))
      (node (ref "X3") (pin "12") (pinfunction "12_12") (pintype "passive"))
    )
    (net (code "136") (name "Net-(K12A-CB)") (class "Default")
      (node (ref "K12") (pin "4") (pinfunction "CB_4") (pintype "passive"))
      (node (ref "X2") (pin "12") (pinfunction "12_12") (pintype "passive"))
    )
    (net (code "137") (name "Net-(K12B--)") (class "Default")
      (node (ref "K12") (pin "2") (pinfunction "-_2") (pintype "passive"))
      (node (ref "Q12") (pin "3") (pinfunction "D_3") (pintype "passive"))
    )
    (net (code "138") (name "Net-(K13A-CA)") (class "Default")
      (node (ref "K13") (pin "3") (pinfunction "CA_3") (pintype "passive"))
      (node (ref "X3") (pin "13") (pinfunction "13_13") (pintype "passive"))
    )
    (net (code "139") (name "Net-(K13A-CB)") (class "Default")
      (node (ref "K13") (pin "4") (pinfunction "CB_4") (pintype "passive"))
      (node (ref "X2") (pin "13") (pinfunction "13_13") (pintype "passive"))
    )
    (net (code "140") (name "Net-(K13B--)") (class "Default")
      (node (ref "K13") (pin "2") (pinfunction "-_2") (pintype "passive"))
      (node (ref "Q13") (pin "3") (pinfunction "D_3") (pintype "passive"))
    )
    (net (code "141") (name "Net-(K14A-CA)") (class "Default")
      (node (ref "K14") (pin "3") (pinfunction "CA_3") (pintype "passive"))
      (node (ref "X3") (pin "14") (pinfunction "14_14") (pintype "passive"))
    )
    (net (code "142") (name "Net-(K14A-CB)") (class "Default")
      (node (ref "K14") (pin "4") (pinfunction "CB_4") (pintype "passive"))
      (node (ref "X2") (pin "14") (pinfunction "14_14") (pintype "passive"))
    )
    (net (code "143") (name "Net-(K14B--)") (class "Default")
      (node (ref "K14") (pin "2") (pinfunction "-_2") (pintype "passive"))
      (node (ref "Q14") (pin "3") (pinfunction "D_3") (pintype "passive"))
    )
    (net (code "144") (name "Net-(K15A-CA)") (class "Default")
      (node (ref "K15") (pin "3") (pinfunction "CA_3") (pintype "passive"))
      (node (ref "X3") (pin "15") (pinfunction "15_15") (pintype "passive"))
    )
    (net (code "145") (name "Net-(K15A-CB)") (class "Default")
      (node (ref "K15") (pin "4") (pinfunction "CB_4") (pintype "passive"))
      (node (ref "X2") (pin "15") (pinfunction "15_15") (pintype "passive"))
    )
    (net (code "146") (name "Net-(K15B--)") (class "Default")
      (node (ref "K15") (pin "2") (pinfunction "-_2") (pintype "passive"))
      (node (ref "Q15") (pin "3") (pinfunction "D_3") (pintype "passive"))
    )
    (net (code "147") (name "Net-(K16A-CA)") (class "Default")
      (node (ref "K16") (pin "3") (pinfunction "CA_3") (pintype "passive"))
      (node (ref "X3") (pin "16") (pinfunction "16_16") (pintype "passive"))
    )
    (net (code "148") (name "Net-(K16A-CB)") (class "Default")
      (node (ref "K16") (pin "4") (pinfunction "CB_4") (pintype "passive"))
      (node (ref "X2") (pin "16") (pinfunction "16_16") (pintype "passive"))
    )
    (net (code "149") (name "Net-(K16B--)") (class "Default")
      (node (ref "K16") (pin "2") (pinfunction "-_2") (pintype "passive"))
      (node (ref "Q16") (pin "3") (pinfunction "D_3") (pintype "passive"))
    )
    (net (code "150") (name "Net-(K17A-CA)") (class "Default")
      (node (ref "K17") (pin "3") (pinfunction "CA_3") (pintype "passive"))
      (node (ref "X3") (pin "17") (pinfunction "17_17") (pintype "passive"))
    )
    (net (code "151") (name "Net-(K17A-CB)") (class "Default")
      (node (ref "K17") (pin "4") (pinfunction "CB_4") (pintype "passive"))
      (node (ref "X2") (pin "17") (pinfunction "17_17") (pintype "passive"))
    )
    (net (code "152") (name "Net-(K17B--)") (class "Default")
      (node (ref "K17") (pin "2") (pinfunction "-_2") (pintype "passive"))
      (node (ref "Q17") (pin "3") (pinfunction "D_3") (pintype "passive"))
    )
    (net (code "153") (name "Net-(K18A-CA)") (class "Default")
      (node (ref "K18") (pin "3") (pinfunction "CA_3") (pintype "passive"))
      (node (ref "X3") (pin "18") (pinfunction "18_18") (pintype "passive"))
    )
    (net (code "154") (name "Net-(K18A-CB)") (class "Default")
      (node (ref "K18") (pin "4") (pinfunction "CB_4") (pintype "passive"))
      (node (ref "X2") (pin "18") (pinfunction "18_18") (pintype "passive"))
    )
    (net (code "155") (name "Net-(K18B--)") (class "Default")
      (node (ref "K18") (pin "2") (pinfunction "-_2") (pintype "passive"))
      (node (ref "Q18") (pin "3") (pinfunction "D_3") (pintype "passive"))
    )
    (net (code "156") (name "Net-(K19A-CA)") (class "Default")
      (node (ref "K19") (pin "3") (pinfunction "CA_3") (pintype "passive"))
      (node (ref "X3") (pin "19") (pinfunction "19_19") (pintype "passive"))
    )
    (net (code "157") (name "Net-(K19A-CB)") (class "Default")
      (node (ref "K19") (pin "4") (pinfunction "CB_4") (pintype "passive"))
      (node (ref "X2") (pin "19") (pinfunction "19_19") (pintype "passive"))
    )
    (net (code "158") (name "Net-(K19B--)") (class "Default")
      (node (ref "K19") (pin "2") (pinfunction "-_2") (pintype "passive"))
      (node (ref "Q19") (pin "3") (pinfunction "D_3") (pintype "passive"))
    )
    (net (code "159") (name "Net-(K20A-CA)") (class "Default")
      (node (ref "K20") (pin "3") (pinfunction "CA_3") (pintype "passive"))
      (node (ref "X3") (pin "20") (pinfunction "20_20") (pintype "passive"))
    )
    (net (code "160") (name "Net-(K20A-CB)") (class "Default")
      (node (ref "K20") (pin "4") (pinfunction "CB_4") (pintype "passive"))
      (node (ref "X2") (pin "20") (pinfunction "20_20") (pintype "passive"))
    )
    (net (code "161") (name "Net-(K20B--)") (class "Default")
      (node (ref "K20") (pin "2") (pinfunction "-_2") (pintype "passive"))
      (node (ref "Q20") (pin "3") (pinfunction "D_3") (pintype "passive"))
    )
    (net (code "162") (name "Net-(K21A-CA)") (class "Default")
      (node (ref "K21") (pin "3") (pinfunction "CA_3") (pintype "passive"))
      (node (ref "X3") (pin "21") (pinfunction "21_21") (pintype "passive"))
    )
    (net (code "163") (name "Net-(K21A-CB)") (class "Default")
      (node (ref "K21") (pin "4") (pinfunction "CB_4") (pintype "passive"))
      (node (ref "X2") (pin "21") (pinfunction "21_21") (pintype "passive"))
    )
    (net (code "164") (name "Net-(K21B--)") (class "Default")
      (node (ref "K21") (pin "2") (pinfunction "-_2") (pintype "passive"))
      (node (ref "Q21") (pin "3") (pinfunction "D_3") (pintype "passive"))
    )
    (net (code "165") (name "Net-(K22A-CA)") (class "Default")
      (node (ref "K22") (pin "3") (pinfunction "CA_3") (pintype "passive"))
      (node (ref "X3") (pin "22") (pinfunction "22_22") (pintype "passive"))
    )
    (net (code "166") (name "Net-(K22A-CB)") (class "Default")
      (node (ref "K22") (pin "4") (pinfunction "CB_4") (pintype "passive"))
      (node (ref "X2") (pin "22") (pinfunction "22_22") (pintype "passive"))
    )
    (net (code "167") (name "Net-(K22B--)") (class "Default")
      (node (ref "K22") (pin "2") (pinfunction "-_2") (pintype "passive"))
      (node (ref "Q22") (pin "3") (pinfunction "D_3") (pintype "passive"))
    )
    (net (code "168") (name "Net-(K23A-CA)") (class "Default")
      (node (ref "K23") (pin "3") (pinfunction "CA_3") (pintype "passive"))
      (node (ref "X3") (pin "23") (pinfunction "23_23") (pintype "passive"))
    )
    (net (code "169") (name "Net-(K23A-CB)") (class "Default")
      (node (ref "K23") (pin "4") (pinfunction "CB_4") (pintype "passive"))
      (node (ref "X2") (pin "23") (pinfunction "23_23") (pintype "passive"))
    )
    (net (code "170") (name "Net-(K23B--)") (class "Default")
      (node (ref "K23") (pin "2") (pinfunction "-_2") (pintype "passive"))
      (node (ref "Q23") (pin "3") (pinfunction "D_3") (pintype "passive"))
    )
    (net (code "171") (name "Net-(K24A-CA)") (class "Default")
      (node (ref "K24") (pin "3") (pinfunction "CA_3") (pintype "passive"))
      (node (ref "X3") (pin "24") (pinfunction "24_24") (pintype "passive"))
    )
    (net (code "172") (name "Net-(K24A-CB)") (class "Default")
      (node (ref "K24") (pin "4") (pinfunction "CB_4") (pintype "passive"))
      (node (ref "X2") (pin "24") (pinfunction "24_24") (pintype "passive"))
    )
    (net (code "173") (name "Net-(K24B--)") (class "Default")
      (node (ref "K24") (pin "2") (pinfunction "-_2") (pintype "passive"))
      (node (ref "Q24") (pin "3") (pinfunction "D_3") (pintype "passive"))
    )
    (net (code "174") (name "Net-(K25A-CA)") (class "Default")
      (node (ref "K25") (pin "3") (pinfunction "CA_3") (pintype "passive"))
      (node (ref "X3") (pin "25") (pinfunction "25_25") (pintype "passive"))
    )
    (net (code "175") (name "Net-(K25A-CB)") (class "Default")
      (node (ref "K25") (pin "4") (pinfunction "CB_4") (pintype "passive"))
      (node (ref "X2") (pin "25") (pinfunction "25_25") (pintype "passive"))
    )
    (net (code "176") (name "Net-(K25B--)") (class "Default")
      (node (ref "K25") (pin "2") (pinfunction "-_2") (pintype "passive"))
      (node (ref "Q25") (pin "3") (pinfunction "D_3") (pintype "passive"))
    )
    (net (code "177") (name "Net-(K26A-CA)") (class "Default")
      (node (ref "K26") (pin "3") (pinfunction "CA_3") (pintype "passive"))
      (node (ref "X3") (pin "26") (pinfunction "26_26") (pintype "passive"))
    )
    (net (code "178") (name "Net-(K26A-CB)") (class "Default")
      (node (ref "K26") (pin "4") (pinfunction "CB_4") (pintype "passive"))
      (node (ref "X2") (pin "26") (pinfunction "26_26") (pintype "passive"))
    )
    (net (code "179") (name "Net-(K26B--)") (class "Default")
      (node (ref "K26") (pin "2") (pinfunction "-_2") (pintype "passive"))
      (node (ref "Q26") (pin "3") (pinfunction "D_3") (pintype "passive"))
    )
    (net (code "180") (name "Net-(K27A-CA)") (class "Default")
      (node (ref "K27") (pin "3") (pinfunction "CA_3") (pintype "passive"))
      (node (ref "X3") (pin "27") (pinfunction "27_27") (pintype "passive"))
    )
    (net (code "181") (name "Net-(K27A-CB)") (class "Default")
      (node (ref "K27") (pin "4") (pinfunction "CB_4") (pintype "passive"))
      (node (ref "X2") (pin "27") (pinfunction "27_27") (pintype "passive"))
    )
    (net (code "182") (name "Net-(K27B--)") (class "Default")
      (node (ref "K27") (pin "2") (pinfunction "-_2") (pintype "passive"))
      (node (ref "Q27") (pin "3") (pinfunction "D_3") (pintype "passive"))
    )
    (net (code "183") (name "Net-(K28A-CA)") (class "Default")
      (node (ref "K28") (pin "3") (pinfunction "CA_3") (pintype "passive"))
      (node (ref "X3") (pin "28") (pinfunction "28_28") (pintype "passive"))
    )
    (net (code "184") (name "Net-(K28A-CB)") (class "Default")
      (node (ref "K28") (pin "4") (pinfunction "CB_4") (pintype "passive"))
      (node (ref "X2") (pin "28") (pinfunction "28_28") (pintype "passive"))
    )
    (net (code "185") (name "Net-(K28B--)") (class "Default")
      (node (ref "K28") (pin "2") (pinfunction "-_2") (pintype "passive"))
      (node (ref "Q28") (pin "3") (pinfunction "D_3") (pintype "passive"))
    )
    (net (code "186") (name "Net-(K29A-CA)") (class "Default")
      (node (ref "K29") (pin "3") (pinfunction "CA_3") (pintype "passive"))
      (node (ref "X3") (pin "29") (pinfunction "29_29") (pintype "passive"))
    )
    (net (code "187") (name "Net-(K29A-CB)") (class "Default")
      (node (ref "K29") (pin "4") (pinfunction "CB_4") (pintype "passive"))
      (node (ref "X2") (pin "29") (pinfunction "29_29") (pintype "passive"))
    )
    (net (code "188") (name "Net-(K29B--)") (class "Default")
      (node (ref "K29") (pin "2") (pinfunction "-_2") (pintype "passive"))
      (node (ref "Q29") (pin "3") (pinfunction "D_3") (pintype "passive"))
    )
    (net (code "189") (name "Net-(K30A-CA)") (class "Default")
      (node (ref "K30") (pin "3") (pinfunction "CA_3") (pintype "passive"))
      (node (ref "X3") (pin "30") (pinfunction "30_30") (pintype "passive"))
    )
    (net (code "190") (name "Net-(K30A-CB)") (class "Default")
      (node (ref "K30") (pin "4") (pinfunction "CB_4") (pintype "passive"))
      (node (ref "X2") (pin "30") (pinfunction "30_30") (pintype "passive"))
    )
    (net (code "191") (name "Net-(K30B--)") (class "Default")
      (node (ref "K30") (pin "2") (pinfunction "-_2") (pintype "passive"))
      (node (ref "Q30") (pin "3") (pinfunction "D_3") (pintype "passive"))
    )
    (net (code "192") (name "Net-(K31A-CA)") (class "Default")
      (node (ref "K31") (pin "3") (pinfunction "CA_3") (pintype "passive"))
      (node (ref "X3") (pin "31") (pinfunction "31_31") (pintype "passive"))
    )
    (net (code "193") (name "Net-(K31A-CB)") (class "Default")
      (node (ref "K31") (pin "4") (pinfunction "CB_4") (pintype "passive"))
      (node (ref "X2") (pin "31") (pinfunction "31_31") (pintype "passive"))
    )
    (net (code "194") (name "Net-(K31B--)") (class "Default")
      (node (ref "K31") (pin "2") (pinfunction "-_2") (pintype "passive"))
      (node (ref "Q31") (pin "3") (pinfunction "D_3") (pintype "passive"))
    )
    (net (code "195") (name "Net-(K32A-CA)") (class "Default")
      (node (ref "K32") (pin "3") (pinfunction "CA_3") (pintype "passive"))
      (node (ref "X3") (pin "32") (pinfunction "32_32") (pintype "passive"))
    )
    (net (code "196") (name "Net-(K32A-CB)") (class "Default")
      (node (ref "K32") (pin "4") (pinfunction "CB_4") (pintype "passive"))
      (node (ref "X2") (pin "32") (pinfunction "32_32") (pintype "passive"))
    )
    (net (code "197") (name "Net-(K32B--)") (class "Default")
      (node (ref "K32") (pin "2") (pinfunction "-_2") (pintype "passive"))
      (node (ref "Q32") (pin "3") (pinfunction "D_3") (pintype "passive"))
    )
    (net (code "198") (name "Net-(K33A-CA)") (class "Default")
      (node (ref "K33") (pin "3") (pinfunction "CA_3") (pintype "passive"))
      (node (ref "X3") (pin "33") (pinfunction "33_33") (pintype "passive"))
    )
    (net (code "199") (name "Net-(K33A-CB)") (class "Default")
      (node (ref "K33") (pin "4") (pinfunction "CB_4") (pintype "passive"))
      (node (ref "X2") (pin "33") (pinfunction "33_33") (pintype "passive"))
    )
    (net (code "200") (name "Net-(K33B--)") (class "Default")
      (node (ref "K33") (pin "2") (pinfunction "-_2") (pintype "passive"))
      (node (ref "Q33") (pin "3") (pinfunction "D_3") (pintype "passive"))
    )
    (net (code "201") (name "Net-(K34A-CA)") (class "Default")
      (node (ref "K34") (pin "3") (pinfunction "CA_3") (pintype "passive"))
      (node (ref "X3") (pin "34") (pinfunction "34_34") (pintype "passive"))
    )
    (net (code "202") (name "Net-(K34A-CB)") (class "Default")
      (node (ref "K34") (pin "4") (pinfunction "CB_4") (pintype "passive"))
      (node (ref "X2") (pin "34") (pinfunction "34_34") (pintype "passive"))
    )
    (net (code "203") (name "Net-(K34B--)") (class "Default")
      (node (ref "K34") (pin "2") (pinfunction "-_2") (pintype "passive"))
      (node (ref "Q34") (pin "3") (pinfunction "D_3") (pintype "passive"))
    )
    (net (code "204") (name "Net-(K35A-CA)") (class "Default")
      (node (ref "K35") (pin "3") (pinfunction "CA_3") (pintype "passive"))
      (node (ref "X3") (pin "35") (pinfunction "35_35") (pintype "passive"))
    )
    (net (code "205") (name "Net-(K35A-CB)") (class "Default")
      (node (ref "K35") (pin "4") (pinfunction "CB_4") (pintype "passive"))
      (node (ref "X2") (pin "35") (pinfunction "35_35") (pintype "passive"))
    )
    (net (code "206") (name "Net-(K35B--)") (class "Default")
      (node (ref "K35") (pin "2") (pinfunction "-_2") (pintype "passive"))
      (node (ref "Q35") (pin "3") (pinfunction "D_3") (pintype "passive"))
    )
    (net (code "207") (name "Net-(K36A-CA)") (class "Default")
      (node (ref "K36") (pin "3") (pinfunction "CA_3") (pintype "passive"))
      (node (ref "X3") (pin "36") (pinfunction "36_36") (pintype "passive"))
    )
    (net (code "208") (name "Net-(K36A-CB)") (class "Default")
      (node (ref "K36") (pin "4") (pinfunction "CB_4") (pintype "passive"))
      (node (ref "X2") (pin "36") (pinfunction "36_36") (pintype "passive"))
    )
    (net (code "209") (name "Net-(K36B--)") (class "Default")
      (node (ref "K36") (pin "2") (pinfunction "-_2") (pintype "passive"))
      (node (ref "Q36") (pin "3") (pinfunction "D_3") (pintype "passive"))
    )
    (net (code "210") (name "Net-(K37A-CA)") (class "Default")
      (node (ref "K37") (pin "3") (pinfunction "CA_3") (pintype "passive"))
      (node (ref "X3") (pin "37") (pinfunction "37_37") (pintype "passive"))
    )
    (net (code "211") (name "Net-(K37A-CB)") (class "Default")
      (node (ref "K37") (pin "4") (pinfunction "CB_4") (pintype "passive"))
      (node (ref "X2") (pin "37") (pinfunction "37_37") (pintype "passive"))
    )
    (net (code "212") (name "Net-(K37B--)") (class "Default")
      (node (ref "K37") (pin "2") (pinfunction "-_2") (pintype "passive"))
      (node (ref "Q37") (pin "3") (pinfunction "D_3") (pintype "passive"))
    )
    (net (code "213") (name "Net-(K38A-CA)") (class "Default")
      (node (ref "K38") (pin "3") (pinfunction "CA_3") (pintype "passive"))
      (node (ref "X3") (pin "38") (pinfunction "38_38") (pintype "passive"))
    )
    (net (code "214") (name "Net-(K38A-CB)") (class "Default")
      (node (ref "K38") (pin "4") (pinfunction "CB_4") (pintype "passive"))
      (node (ref "X2") (pin "38") (pinfunction "38_38") (pintype "passive"))
    )
    (net (code "215") (name "Net-(K38B--)") (class "Default")
      (node (ref "K38") (pin "2") (pinfunction "-_2") (pintype "passive"))
      (node (ref "Q38") (pin "3") (pinfunction "D_3") (pintype "passive"))
    )
    (net (code "216") (name "Net-(K39A-CA)") (class "Default")
      (node (ref "K39") (pin "3") (pinfunction "CA_3") (pintype "passive"))
      (node (ref "X3") (pin "39") (pinfunction "39_39") (pintype "passive"))
    )
    (net (code "217") (name "Net-(K39A-CB)") (class "Default")
      (node (ref "K39") (pin "4") (pinfunction "CB_4") (pintype "passive"))
      (node (ref "X2") (pin "39") (pinfunction "39_39") (pintype "passive"))
    )
    (net (code "218") (name "Net-(K39B--)") (class "Default")
      (node (ref "K39") (pin "2") (pinfunction "-_2") (pintype "passive"))
      (node (ref "Q39") (pin "3") (pinfunction "D_3") (pintype "passive"))
    )
    (net (code "219") (name "Net-(K40A-CA)") (class "Default")
      (node (ref "K40") (pin "3") (pinfunction "CA_3") (pintype "passive"))
      (node (ref "X3") (pin "40") (pinfunction "40_40") (pintype "passive"))
    )
    (net (code "220") (name "Net-(K40A-CB)") (class "Default")
      (node (ref "K40") (pin "4") (pinfunction "CB_4") (pintype "passive"))
      (node (ref "X2") (pin "40") (pinfunction "40_40") (pintype "passive"))
    )
    (net (code "221") (name "Net-(K40B--)") (class "Default")
      (node (ref "K40") (pin "2") (pinfunction "-_2") (pintype "passive"))
      (node (ref "Q40") (pin "3") (pinfunction "D_3") (pintype "passive"))
    )
    (net (code "222") (name "Net-(K41A-CA)") (class "Default")
      (node (ref "K41") (pin "3") (pinfunction "CA_3") (pintype "passive"))
      (node (ref "X3") (pin "41") (pinfunction "41_41") (pintype "passive"))
    )
    (net (code "223") (name "Net-(K41A-CB)") (class "Default")
      (node (ref "K41") (pin "4") (pinfunction "CB_4") (pintype "passive"))
      (node (ref "X2") (pin "41") (pinfunction "41_41") (pintype "passive"))
    )
    (net (code "224") (name "Net-(K41B--)") (class "Default")
      (node (ref "K41") (pin "2") (pinfunction "-_2") (pintype "passive"))
      (node (ref "Q41") (pin "3") (pinfunction "D_3") (pintype "passive"))
    )
    (net (code "225") (name "Net-(K42A-CA)") (class "Default")
      (node (ref "K42") (pin "3") (pinfunction "CA_3") (pintype "passive"))
      (node (ref "X3") (pin "42") (pinfunction "42_42") (pintype "passive"))
    )
    (net (code "226") (name "Net-(K42A-CB)") (class "Default")
      (node (ref "K42") (pin "4") (pinfunction "CB_4") (pintype "passive"))
      (node (ref "X2") (pin "42") (pinfunction "42_42") (pintype "passive"))
    )
    (net (code "227") (name "Net-(K42B--)") (class "Default")
      (node (ref "K42") (pin "2") (pinfunction "-_2") (pintype "passive"))
      (node (ref "Q42") (pin "3") (pinfunction "D_3") (pintype "passive"))
    )
    (net (code "228") (name "Net-(K43A-CA)") (class "Default")
      (node (ref "K43") (pin "3") (pinfunction "CA_3") (pintype "passive"))
      (node (ref "X3") (pin "43") (pinfunction "43_43") (pintype "passive"))
    )
    (net (code "229") (name "Net-(K43A-CB)") (class "Default")
      (node (ref "K43") (pin "4") (pinfunction "CB_4") (pintype "passive"))
      (node (ref "X2") (pin "43") (pinfunction "43_43") (pintype "passive"))
    )
    (net (code "230") (name "Net-(K43B--)") (class "Default")
      (node (ref "K43") (pin "2") (pinfunction "-_2") (pintype "passive"))
      (node (ref "Q43") (pin "3") (pinfunction "D_3") (pintype "passive"))
    )
    (net (code "231") (name "Net-(K44A-CA)") (class "Default")
      (node (ref "K44") (pin "3") (pinfunction "CA_3") (pintype "passive"))
      (node (ref "X3") (pin "44") (pinfunction "44_44") (pintype "passive"))
    )
    (net (code "232") (name "Net-(K44A-CB)") (class "Default")
      (node (ref "K44") (pin "4") (pinfunction "CB_4") (pintype "passive"))
      (node (ref "X2") (pin "44") (pinfunction "44_44") (pintype "passive"))
    )
    (net (code "233") (name "Net-(K44B--)") (class "Default")
      (node (ref "K44") (pin "2") (pinfunction "-_2") (pintype "passive"))
      (node (ref "Q44") (pin "3") (pinfunction "D_3") (pintype "passive"))
    )
    (net (code "234") (name "Net-(K45A-CA)") (class "Default")
      (node (ref "K45") (pin "3") (pinfunction "CA_3") (pintype "passive"))
      (node (ref "X3") (pin "45") (pinfunction "45_45") (pintype "passive"))
    )
    (net (code "235") (name "Net-(K45A-CB)") (class "Default")
      (node (ref "K45") (pin "4") (pinfunction "CB_4") (pintype "passive"))
      (node (ref "X2") (pin "45") (pinfunction "45_45") (pintype "passive"))
    )
    (net (code "236") (name "Net-(K45B--)") (class "Default")
      (node (ref "K45") (pin "2") (pinfunction "-_2") (pintype "passive"))
      (node (ref "Q45") (pin "3") (pinfunction "D_3") (pintype "passive"))
    )
    (net (code "237") (name "Net-(K46A-CA)") (class "Default")
      (node (ref "K46") (pin "3") (pinfunction "CA_3") (pintype "passive"))
      (node (ref "X3") (pin "46") (pinfunction "46_46") (pintype "passive"))
    )
    (net (code "238") (name "Net-(K46A-CB)") (class "Default")
      (node (ref "K46") (pin "4") (pinfunction "CB_4") (pintype "passive"))
      (node (ref "X2") (pin "46") (pinfunction "46_46") (pintype "passive"))
    )
    (net (code "239") (name "Net-(K46B--)") (class "Default")
      (node (ref "K46") (pin "2") (pinfunction "-_2") (pintype "passive"))
      (node (ref "Q46") (pin "3") (pinfunction "D_3") (pintype "passive"))
    )
    (net (code "240") (name "Net-(K47A-CA)") (class "Default")
      (node (ref "K47") (pin "3") (pinfunction "CA_3") (pintype "passive"))
      (node (ref "X3") (pin "47") (pinfunction "47_47") (pintype "passive"))
    )
    (net (code "241") (name "Net-(K47A-CB)") (class "Default")
      (node (ref "K47") (pin "4") (pinfunction "CB_4") (pintype "passive"))
      (node (ref "X2") (pin "47") (pinfunction "47_47") (pintype "passive"))
    )
    (net (code "242") (name "Net-(K47B--)") (class "Default")
      (node (ref "K47") (pin "2") (pinfunction "-_2") (pintype "passive"))
      (node (ref "Q47") (pin "3") (pinfunction "D_3") (pintype "passive"))
    )
    (net (code "243") (name "Net-(K48A-CA)") (class "Default")
      (node (ref "K48") (pin "3") (pinfunction "CA_3") (pintype "passive"))
      (node (ref "X3") (pin "48") (pinfunction "48_48") (pintype "passive"))
    )
    (net (code "244") (name "Net-(K48A-CB)") (class "Default")
      (node (ref "K48") (pin "4") (pinfunction "CB_4") (pintype "passive"))
      (node (ref "X2") (pin "48") (pinfunction "48_48") (pintype "passive"))
    )
    (net (code "245") (name "Net-(K48B--)") (class "Default")
      (node (ref "K48") (pin "2") (pinfunction "-_2") (pintype "passive"))
      (node (ref "Q48") (pin "3") (pinfunction "D_3") (pintype "passive"))
    )
    (net (code "246") (name "Net-(K49A-CA)") (class "Default")
      (node (ref "K49") (pin "3") (pinfunction "CA_3") (pintype "passive"))
      (node (ref "X3") (pin "49") (pinfunction "49_49") (pintype "passive"))
    )
    (net (code "247") (name "Net-(K49A-CB)") (class "Default")
      (node (ref "K49") (pin "4") (pinfunction "CB_4") (pintype "passive"))
      (node (ref "X2") (pin "49") (pinfunction "49_49") (pintype "passive"))
    )
    (net (code "248") (name "Net-(K49B--)") (class "Default")
      (node (ref "K49") (pin "2") (pinfunction "-_2") (pintype "passive"))
      (node (ref "Q49") (pin "3") (pinfunction "D_3") (pintype "passive"))
    )
    (net (code "249") (name "Net-(K50A-CA)") (class "Default")
      (node (ref "K50") (pin "3") (pinfunction "CA_3") (pintype "passive"))
      (node (ref "X3") (pin "50") (pinfunction "50_50") (pintype "passive"))
    )
    (net (code "250") (name "Net-(K50A-CB)") (class "Default")
      (node (ref "K50") (pin "4") (pinfunction "CB_4") (pintype "passive"))
      (node (ref "X2") (pin "50") (pinfunction "50_50") (pintype "passive"))
    )
    (net (code "251") (name "Net-(K50B--)") (class "Default")
      (node (ref "K50") (pin "2") (pinfunction "-_2") (pintype "passive"))
      (node (ref "Q50") (pin "3") (pinfunction "D_3") (pintype "passive"))
    )
    (net (code "252") (name "Net-(K51A-CA)") (class "Default")
      (node (ref "K51") (pin "3") (pinfunction "CA_3") (pintype "passive"))
      (node (ref "X3") (pin "51") (pinfunction "51_51") (pintype "passive"))
    )
    (net (code "253") (name "Net-(K51A-CB)") (class "Default")
      (node (ref "K51") (pin "4") (pinfunction "CB_4") (pintype "passive"))
      (node (ref "X2") (pin "51") (pinfunction "51_51") (pintype "passive"))
    )
    (net (code "254") (name "Net-(K51B--)") (class "Default")
      (node (ref "K51") (pin "2") (pinfunction "-_2") (pintype "passive"))
      (node (ref "Q51") (pin "3") (pinfunction "D_3") (pintype "passive"))
    )
    (net (code "255") (name "Net-(K52A-CA)") (class "Default")
      (node (ref "K52") (pin "3") (pinfunction "CA_3") (pintype "passive"))
      (node (ref "X3") (pin "52") (pinfunction "52_52") (pintype "passive"))
    )
    (net (code "256") (name "Net-(K52A-CB)") (class "Default")
      (node (ref "K52") (pin "4") (pinfunction "CB_4") (pintype "passive"))
      (node (ref "X2") (pin "52") (pinfunction "52_52") (pintype "passive"))
    )
    (net (code "257") (name "Net-(K52B--)") (class "Default")
      (node (ref "K52") (pin "2") (pinfunction "-_2") (pintype "passive"))
      (node (ref "Q52") (pin "3") (pinfunction "D_3") (pintype "passive"))
    )
    (net (code "258") (name "Net-(K53A-CA)") (class "Default")
      (node (ref "K53") (pin "3") (pinfunction "CA_3") (pintype "passive"))
      (node (ref "X3") (pin "53") (pinfunction "53_53") (pintype "passive"))
    )
    (net (code "259") (name "Net-(K53A-CB)") (class "Default")
      (node (ref "K53") (pin "4") (pinfunction "CB_4") (pintype "passive"))
      (node (ref "X2") (pin "53") (pinfunction "53_53") (pintype "passive"))
    )
    (net (code "260") (name "Net-(K53B--)") (class "Default")
      (node (ref "K53") (pin "2") (pinfunction "-_2") (pintype "passive"))
      (node (ref "Q53") (pin "3") (pinfunction "D_3") (pintype "passive"))
    )
    (net (code "261") (name "Net-(K54A-CA)") (class "Default")
      (node (ref "K54") (pin "3") (pinfunction "CA_3") (pintype "passive"))
      (node (ref "X3") (pin "54") (pinfunction "54_54") (pintype "passive"))
    )
    (net (code "262") (name "Net-(K54A-CB)") (class "Default")
      (node (ref "K54") (pin "4") (pinfunction "CB_4") (pintype "passive"))
      (node (ref "X2") (pin "54") (pinfunction "54_54") (pintype "passive"))
    )
    (net (code "263") (name "Net-(K54B--)") (class "Default")
      (node (ref "K54") (pin "2") (pinfunction "-_2") (pintype "passive"))
      (node (ref "Q54") (pin "3") (pinfunction "D_3") (pintype "passive"))
    )
    (net (code "264") (name "Net-(K55A-CA)") (class "Default")
      (node (ref "K55") (pin "3") (pinfunction "CA_3") (pintype "passive"))
      (node (ref "X3") (pin "55") (pinfunction "55_55") (pintype "passive"))
    )
    (net (code "265") (name "Net-(K55A-CB)") (class "Default")
      (node (ref "K55") (pin "4") (pinfunction "CB_4") (pintype "passive"))
      (node (ref "X2") (pin "55") (pinfunction "55_55") (pintype "passive"))
    )
    (net (code "266") (name "Net-(K55B--)") (class "Default")
      (node (ref "K55") (pin "2") (pinfunction "-_2") (pintype "passive"))
      (node (ref "Q55") (pin "3") (pinfunction "D_3") (pintype "passive"))
    )
    (net (code "267") (name "Net-(K56A-CA)") (class "Default")
      (node (ref "K56") (pin "3") (pinfunction "CA_3") (pintype "passive"))
      (node (ref "X3") (pin "56") (pinfunction "56_56") (pintype "passive"))
    )
    (net (code "268") (name "Net-(K56A-CB)") (class "Default")
      (node (ref "K56") (pin "4") (pinfunction "CB_4") (pintype "passive"))
      (node (ref "X2") (pin "56") (pinfunction "56_56") (pintype "passive"))
    )
    (net (code "269") (name "Net-(K56B--)") (class "Default")
      (node (ref "K56") (pin "2") (pinfunction "-_2") (pintype "passive"))
      (node (ref "Q56") (pin "3") (pinfunction "D_3") (pintype "passive"))
    )
    (net (code "270") (name "Net-(K57A-CA)") (class "Default")
      (node (ref "K57") (pin "3") (pinfunction "CA_3") (pintype "passive"))
      (node (ref "X3") (pin "57") (pinfunction "57_57") (pintype "passive"))
    )
    (net (code "271") (name "Net-(K57A-CB)") (class "Default")
      (node (ref "K57") (pin "4") (pinfunction "CB_4") (pintype "passive"))
      (node (ref "X2") (pin "57") (pinfunction "57_57") (pintype "passive"))
    )
    (net (code "272") (name "Net-(K57B--)") (class "Default")
      (node (ref "K57") (pin "2") (pinfunction "-_2") (pintype "passive"))
      (node (ref "Q57") (pin "3") (pinfunction "D_3") (pintype "passive"))
    )
    (net (code "273") (name "Net-(K58A-CA)") (class "Default")
      (node (ref "K58") (pin "3") (pinfunction "CA_3") (pintype "passive"))
      (node (ref "X3") (pin "58") (pinfunction "58_58") (pintype "passive"))
    )
    (net (code "274") (name "Net-(K58A-CB)") (class "Default")
      (node (ref "K58") (pin "4") (pinfunction "CB_4") (pintype "passive"))
      (node (ref "X2") (pin "58") (pinfunction "58_58") (pintype "passive"))
    )
    (net (code "275") (name "Net-(K58B--)") (class "Default")
      (node (ref "K58") (pin "2") (pinfunction "-_2") (pintype "passive"))
      (node (ref "Q58") (pin "3") (pinfunction "D_3") (pintype "passive"))
    )
    (net (code "276") (name "Net-(K59A-CA)") (class "Default")
      (node (ref "K59") (pin "3") (pinfunction "CA_3") (pintype "passive"))
      (node (ref "X3") (pin "59") (pinfunction "59_59") (pintype "passive"))
    )
    (net (code "277") (name "Net-(K59A-CB)") (class "Default")
      (node (ref "K59") (pin "4") (pinfunction "CB_4") (pintype "passive"))
      (node (ref "X2") (pin "59") (pinfunction "59_59") (pintype "passive"))
    )
    (net (code "278") (name "Net-(K59B--)") (class "Default")
      (node (ref "K59") (pin "2") (pinfunction "-_2") (pintype "passive"))
      (node (ref "Q59") (pin "3") (pinfunction "D_3") (pintype "passive"))
    )
    (net (code "279") (name "Net-(K60A-CA)") (class "Default")
      (node (ref "K60") (pin "3") (pinfunction "CA_3") (pintype "passive"))
      (node (ref "X3") (pin "60") (pinfunction "60_60") (pintype "passive"))
    )
    (net (code "280") (name "Net-(K60A-CB)") (class "Default")
      (node (ref "K60") (pin "4") (pinfunction "CB_4") (pintype "passive"))
      (node (ref "X2") (pin "60") (pinfunction "60_60") (pintype "passive"))
    )
    (net (code "281") (name "Net-(K60B--)") (class "Default")
      (node (ref "K60") (pin "2") (pinfunction "-_2") (pintype "passive"))
      (node (ref "Q60") (pin "3") (pinfunction "D_3") (pintype "passive"))
    )
    (net (code "282") (name "Net-(K61A-CA)") (class "Default")
      (node (ref "K61") (pin "3") (pinfunction "CA_3") (pintype "passive"))
      (node (ref "X3") (pin "61") (pinfunction "61_61") (pintype "passive"))
    )
    (net (code "283") (name "Net-(K61A-CB)") (class "Default")
      (node (ref "K61") (pin "4") (pinfunction "CB_4") (pintype "passive"))
      (node (ref "X2") (pin "61") (pinfunction "61_61") (pintype "passive"))
    )
    (net (code "284") (name "Net-(K61B--)") (class "Default")
      (node (ref "K61") (pin "2") (pinfunction "-_2") (pintype "passive"))
      (node (ref "Q61") (pin "3") (pinfunction "D_3") (pintype "passive"))
    )
    (net (code "285") (name "Net-(K62A-CA)") (class "Default")
      (node (ref "K62") (pin "3") (pinfunction "CA_3") (pintype "passive"))
      (node (ref "X3") (pin "62") (pinfunction "62_62") (pintype "passive"))
    )
    (net (code "286") (name "Net-(K62A-CB)") (class "Default")
      (node (ref "K62") (pin "4") (pinfunction "CB_4") (pintype "passive"))
      (node (ref "X2") (pin "62") (pinfunction "62_62") (pintype "passive"))
    )
    (net (code "287") (name "Net-(K62B--)") (class "Default")
      (node (ref "K62") (pin "2") (pinfunction "-_2") (pintype "passive"))
      (node (ref "Q62") (pin "3") (pinfunction "D_3") (pintype "passive"))
    )
    (net (code "288") (name "Net-(K63A-CA)") (class "Default")
      (node (ref "K63") (pin "3") (pinfunction "CA_3") (pintype "passive"))
      (node (ref "X3") (pin "63") (pinfunction "63_63") (pintype "passive"))
    )
    (net (code "289") (name "Net-(K63A-CB)") (class "Default")
      (node (ref "K63") (pin "4") (pinfunction "CB_4") (pintype "passive"))
      (node (ref "X2") (pin "63") (pinfunction "63_63") (pintype "passive"))
    )
    (net (code "290") (name "Net-(K63B--)") (class "Default")
      (node (ref "K63") (pin "2") (pinfunction "-_2") (pintype "passive"))
      (node (ref "Q63") (pin "3") (pinfunction "D_3") (pintype "passive"))
    )
    (net (code "291") (name "Net-(K64A-CA)") (class "Default")
      (node (ref "K64") (pin "3") (pinfunction "CA_3") (pintype "passive"))
      (node (ref "X3") (pin "64") (pinfunction "64_64") (pintype "passive"))
    )
    (net (code "292") (name "Net-(K64A-CB)") (class "Default")
      (node (ref "K64") (pin "4") (pinfunction "CB_4") (pintype "passive"))
      (node (ref "X2") (pin "64") (pinfunction "64_64") (pintype "passive"))
    )
    (net (code "293") (name "Net-(K64B--)") (class "Default")
      (node (ref "K64") (pin "2") (pinfunction "-_2") (pintype "passive"))
      (node (ref "Q64") (pin "3") (pinfunction "D_3") (pintype "passive"))
    )
  )
)
